# ESC_BOARD_NEW.net
KiCad netlist of a schematic drawn in EAGLE
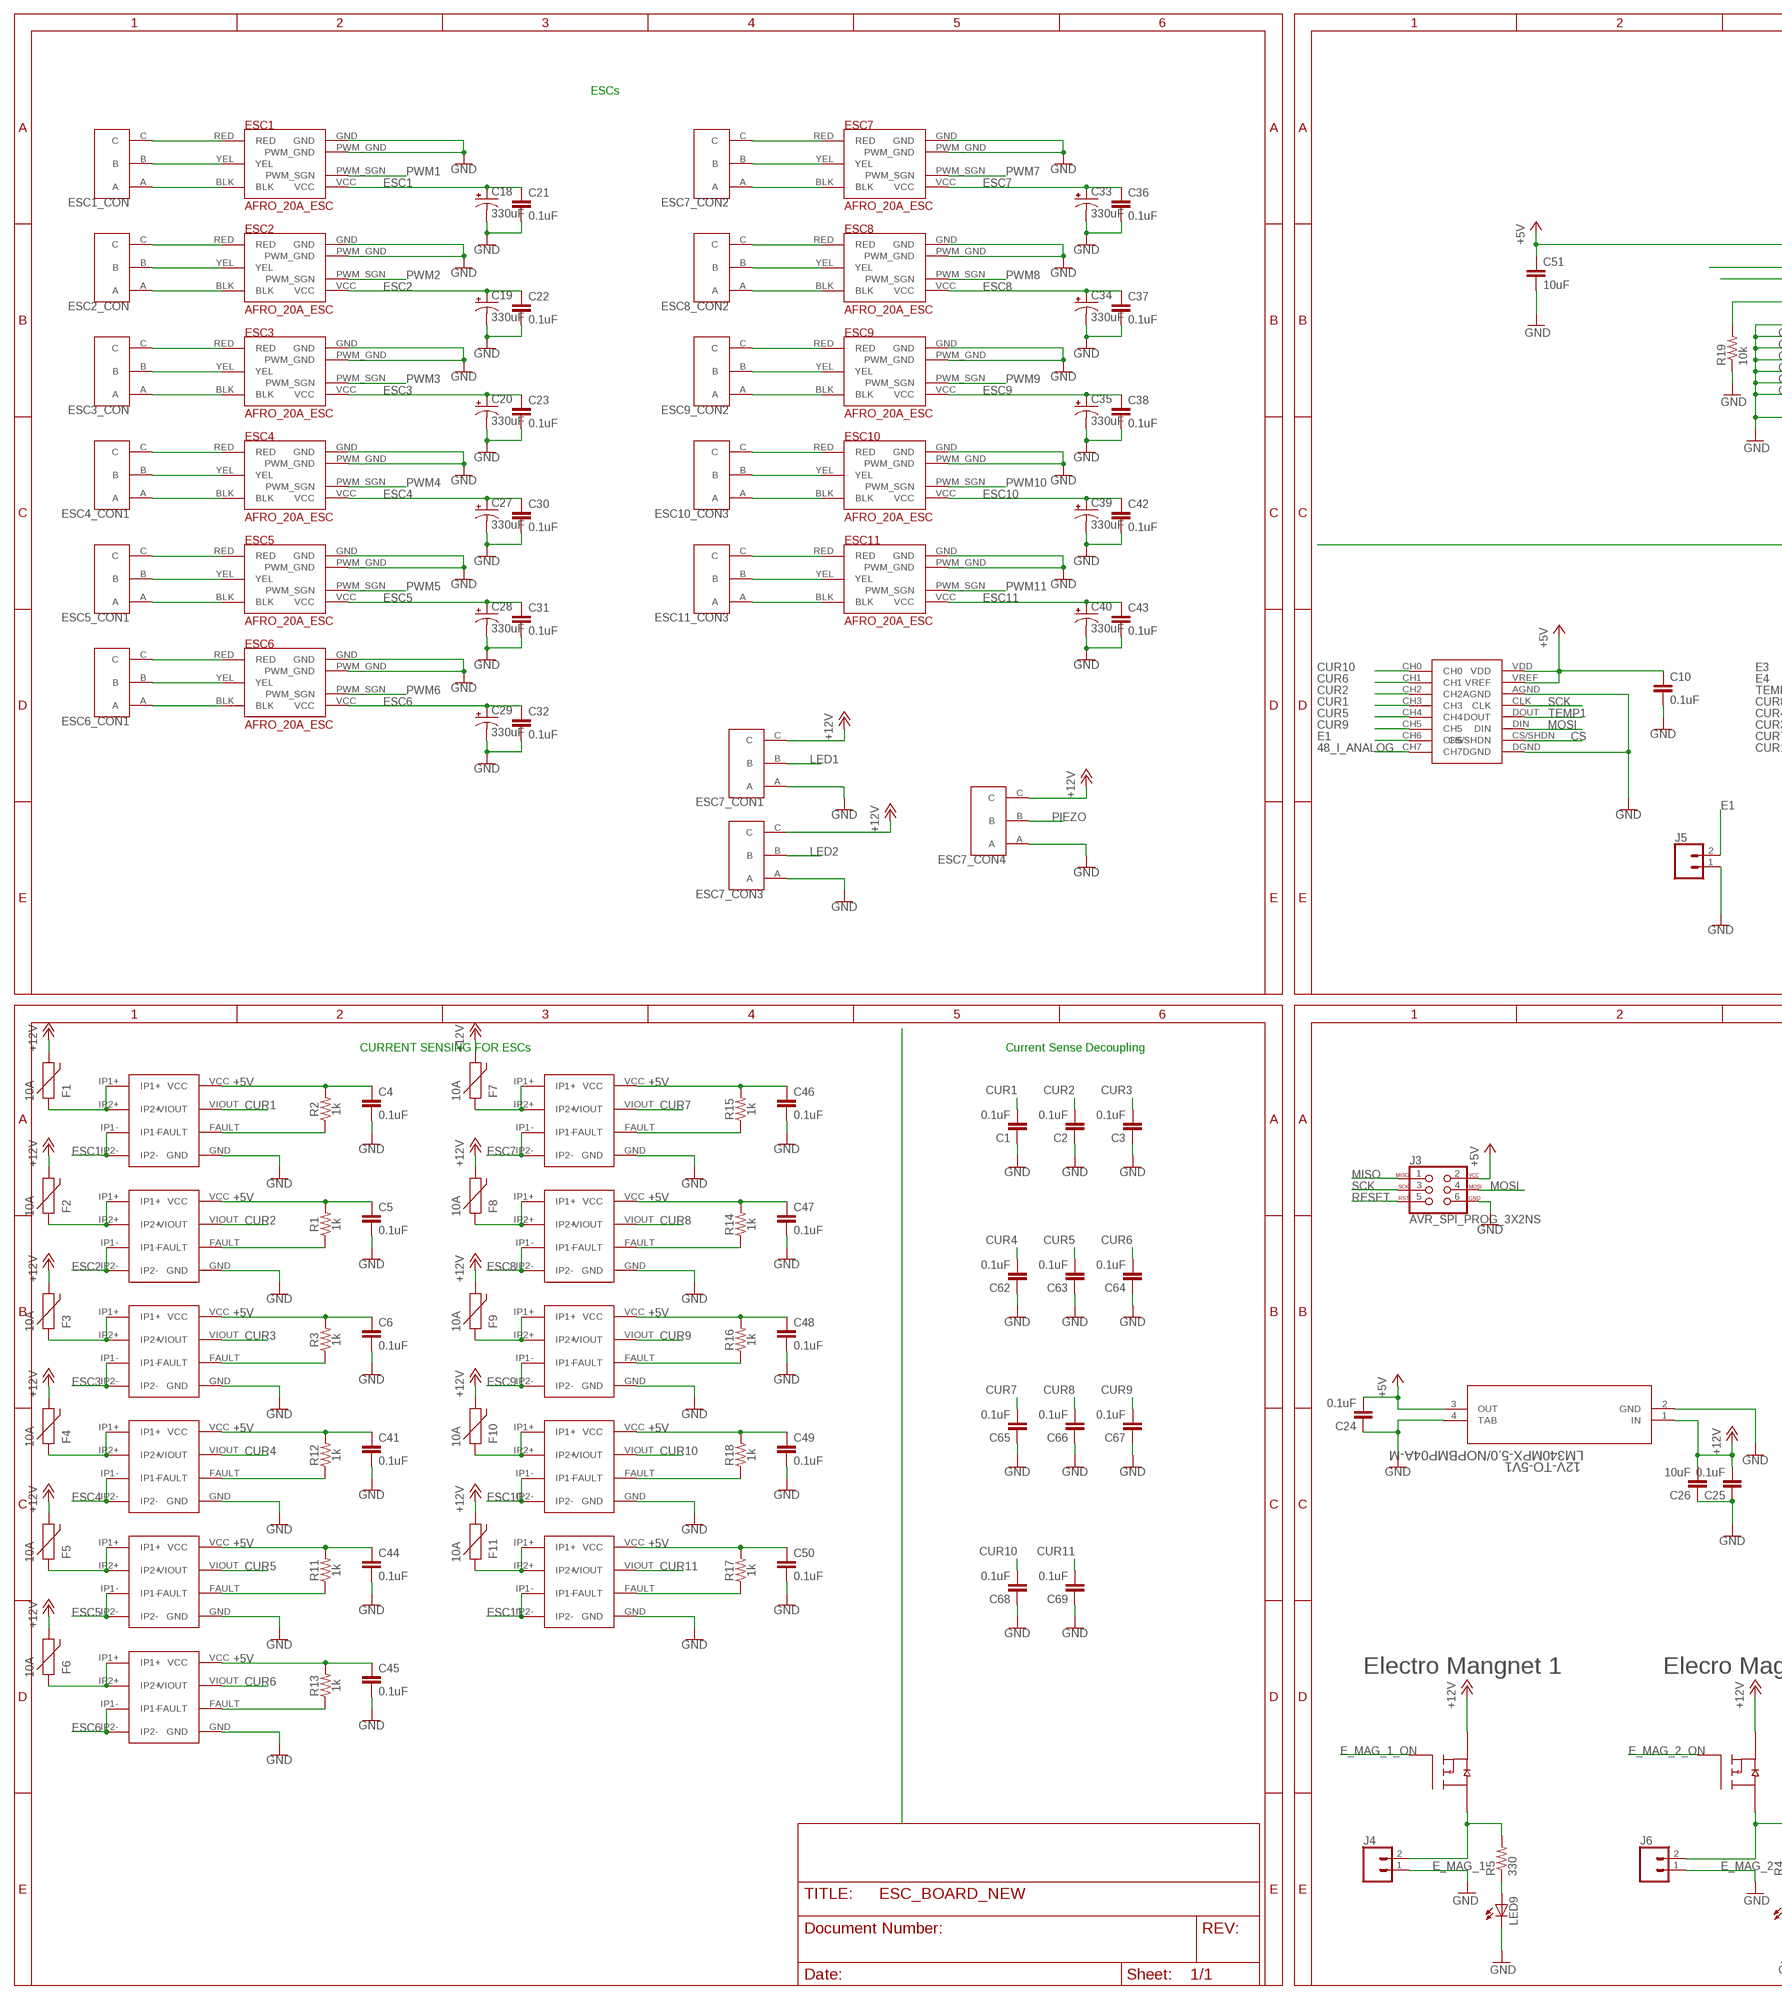
[diagram p0: schematic, sheet 1, part 1 of 2]
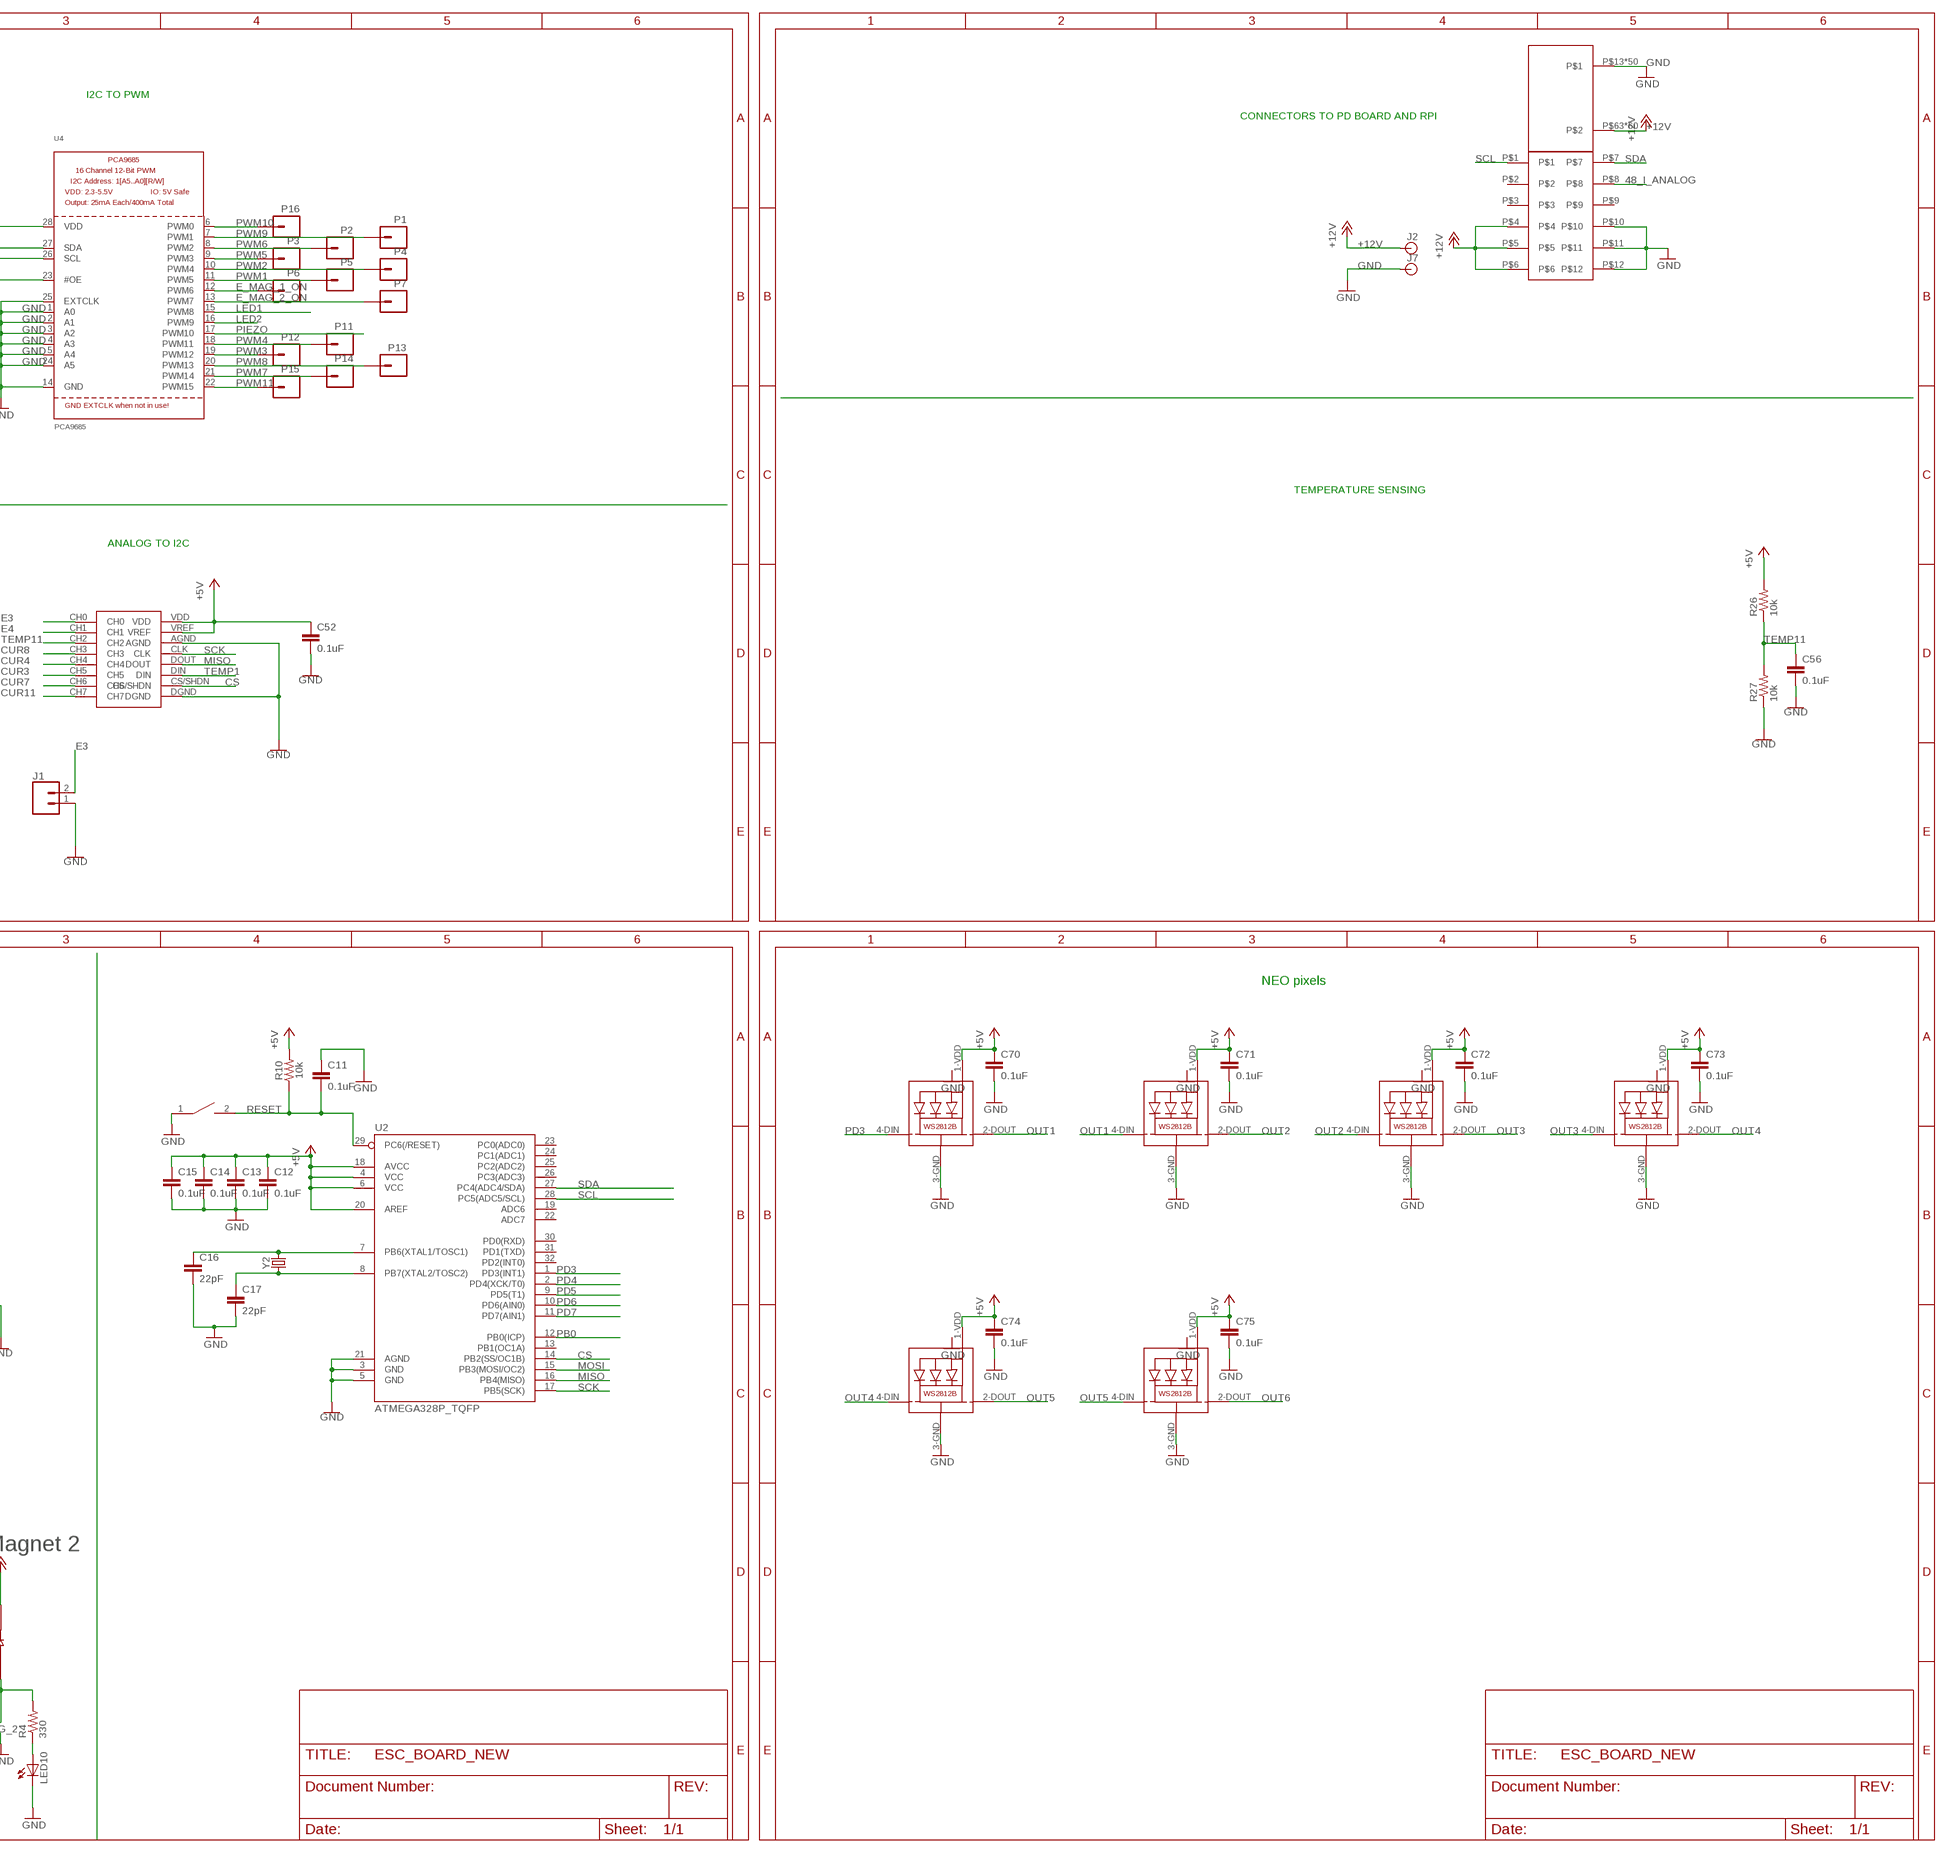
[diagram p1: schematic, sheet 1, part 2 of 2]

(export (version "E")
  (design (tool "Eeschema 10.0.6"))
  (components
    (comp (ref "12V-TO-5V1")
      (value "LM340MPX-5.0/NOPBMP04A-M")
      (footprint "eagle-import:MP04A-M")
      (fields (field (name "MANUFACTURER_PART_NUMBER") "LM340MPX5.0NOPB"))
      (libsource (lib "eagle-import") (part "LM340MPX-5.0/NOPBMP04A-M"))
    )
    (comp (ref "C1")
      (value "0.1uF")
      (footprint "eagle-import:0603")
      (libsource (lib "eagle-import") (part "0.1UF-0603-25V-(+80/-20%)"))
    )
    (comp (ref "C2")
      (value "0.1uF")
      (footprint "eagle-import:0603")
      (libsource (lib "eagle-import") (part "0.1UF-0603-25V-(+80/-20%)"))
    )
    (comp (ref "C3")
      (value "0.1uF")
      (footprint "eagle-import:0603")
      (libsource (lib "eagle-import") (part "0.1UF-0603-25V-(+80/-20%)"))
    )
    (comp (ref "C4")
      (value "0.1uF")
      (footprint "eagle-import:0603")
      (libsource (lib "eagle-import") (part "0.1UF-0603-25V-(+80/-20%)"))
    )
    (comp (ref "C5")
      (value "0.1uF")
      (footprint "eagle-import:0603")
      (libsource (lib "eagle-import") (part "0.1UF-0603-25V-(+80/-20%)"))
    )
    (comp (ref "C6")
      (value "0.1uF")
      (footprint "eagle-import:0603")
      (libsource (lib "eagle-import") (part "0.1UF-0603-25V-(+80/-20%)"))
    )
    (comp (ref "C10")
      (value "0.1uF")
      (footprint "eagle-import:0603")
      (libsource (lib "eagle-import") (part "0.1UF-0603-25V-(+80/-20%)"))
    )
    (comp (ref "C11")
      (value "0.1uF")
      (footprint "eagle-import:C0603")
      (libsource (lib "eagle-import") (part "C-EUC0603"))
    )
    (comp (ref "C12")
      (value "0.1uF")
      (footprint "eagle-import:C0603")
      (libsource (lib "eagle-import") (part "C-EUC0603"))
    )
    (comp (ref "C13")
      (value "0.1uF")
      (footprint "eagle-import:C0603")
      (libsource (lib "eagle-import") (part "C-EUC0603"))
    )
    (comp (ref "C14")
      (value "0.1uF")
      (footprint "eagle-import:C0603")
      (libsource (lib "eagle-import") (part "C-EUC0603"))
    )
    (comp (ref "C15")
      (value "0.1uF")
      (footprint "eagle-import:C0603")
      (libsource (lib "eagle-import") (part "C-EUC0603"))
    )
    (comp (ref "C16")
      (value "22pF")
      (footprint "eagle-import:C0603")
      (libsource (lib "eagle-import") (part "C-EUC0603"))
    )
    (comp (ref "C17")
      (value "22pF")
      (footprint "eagle-import:C0603")
      (libsource (lib "eagle-import") (part "C-EUC0603"))
    )
    (comp (ref "C18")
      (value "330uF")
      (footprint "eagle-import:CPOL-US(10.3_10.3MM)")
      (libsource (lib "eagle-import") (part "C-ALUMINUM(330UF)"))
    )
    (comp (ref "C19")
      (value "330uF")
      (footprint "eagle-import:CPOL-US(10.3_10.3MM)")
      (libsource (lib "eagle-import") (part "C-ALUMINUM(330UF)"))
    )
    (comp (ref "C20")
      (value "330uF")
      (footprint "eagle-import:CPOL-US(10.3_10.3MM)")
      (libsource (lib "eagle-import") (part "C-ALUMINUM(330UF)"))
    )
    (comp (ref "C21")
      (value "0.1uF")
      (footprint "eagle-import:0603")
      (libsource (lib "eagle-import") (part "0.1UF-0603-25V-(+80/-20%)"))
    )
    (comp (ref "C22")
      (value "0.1uF")
      (footprint "eagle-import:0603")
      (libsource (lib "eagle-import") (part "0.1UF-0603-25V-(+80/-20%)"))
    )
    (comp (ref "C23")
      (value "0.1uF")
      (footprint "eagle-import:0603")
      (libsource (lib "eagle-import") (part "0.1UF-0603-25V-(+80/-20%)"))
    )
    (comp (ref "C24")
      (value "0.1uF")
      (footprint "eagle-import:0603")
      (libsource (lib "eagle-import") (part "0.1UF-0603-25V-(+80/-20%)"))
    )
    (comp (ref "C25")
      (value "0.1uF")
      (footprint "eagle-import:0603")
      (libsource (lib "eagle-import") (part "0.1UF-0603-25V-(+80/-20%)"))
    )
    (comp (ref "C26")
      (value "10uF")
      (footprint "eagle-import:0603")
      (libsource (lib "eagle-import") (part "0.1UF-0603-25V-(+80/-20%)"))
    )
    (comp (ref "C27")
      (value "330uF")
      (footprint "eagle-import:CPOL-US(10.3_10.3MM)")
      (libsource (lib "eagle-import") (part "C-ALUMINUM(330UF)"))
    )
    (comp (ref "C28")
      (value "330uF")
      (footprint "eagle-import:CPOL-US(10.3_10.3MM)")
      (libsource (lib "eagle-import") (part "C-ALUMINUM(330UF)"))
    )
    (comp (ref "C29")
      (value "330uF")
      (footprint "eagle-import:CPOL-US(10.3_10.3MM)")
      (libsource (lib "eagle-import") (part "C-ALUMINUM(330UF)"))
    )
    (comp (ref "C30")
      (value "0.1uF")
      (footprint "eagle-import:0603")
      (libsource (lib "eagle-import") (part "0.1UF-0603-25V-(+80/-20%)"))
    )
    (comp (ref "C31")
      (value "0.1uF")
      (footprint "eagle-import:0603")
      (libsource (lib "eagle-import") (part "0.1UF-0603-25V-(+80/-20%)"))
    )
    (comp (ref "C32")
      (value "0.1uF")
      (footprint "eagle-import:0603")
      (libsource (lib "eagle-import") (part "0.1UF-0603-25V-(+80/-20%)"))
    )
    (comp (ref "C33")
      (value "330uF")
      (footprint "eagle-import:CPOL-US(10.3_10.3MM)")
      (libsource (lib "eagle-import") (part "C-ALUMINUM(330UF)"))
    )
    (comp (ref "C34")
      (value "330uF")
      (footprint "eagle-import:CPOL-US(10.3_10.3MM)")
      (libsource (lib "eagle-import") (part "C-ALUMINUM(330UF)"))
    )
    (comp (ref "C35")
      (value "330uF")
      (footprint "eagle-import:CPOL-US(10.3_10.3MM)")
      (libsource (lib "eagle-import") (part "C-ALUMINUM(330UF)"))
    )
    (comp (ref "C36")
      (value "0.1uF")
      (footprint "eagle-import:0603")
      (libsource (lib "eagle-import") (part "0.1UF-0603-25V-(+80/-20%)"))
    )
    (comp (ref "C37")
      (value "0.1uF")
      (footprint "eagle-import:0603")
      (libsource (lib "eagle-import") (part "0.1UF-0603-25V-(+80/-20%)"))
    )
    (comp (ref "C38")
      (value "0.1uF")
      (footprint "eagle-import:0603")
      (libsource (lib "eagle-import") (part "0.1UF-0603-25V-(+80/-20%)"))
    )
    (comp (ref "C39")
      (value "330uF")
      (footprint "eagle-import:CPOL-US(10.3_10.3MM)")
      (libsource (lib "eagle-import") (part "C-ALUMINUM(330UF)"))
    )
    (comp (ref "C40")
      (value "330uF")
      (footprint "eagle-import:CPOL-US(10.3_10.3MM)")
      (libsource (lib "eagle-import") (part "C-ALUMINUM(330UF)"))
    )
    (comp (ref "C41")
      (value "0.1uF")
      (footprint "eagle-import:0603")
      (libsource (lib "eagle-import") (part "0.1UF-0603-25V-(+80/-20%)"))
    )
    (comp (ref "C42")
      (value "0.1uF")
      (footprint "eagle-import:0603")
      (libsource (lib "eagle-import") (part "0.1UF-0603-25V-(+80/-20%)"))
    )
    (comp (ref "C43")
      (value "0.1uF")
      (footprint "eagle-import:0603")
      (libsource (lib "eagle-import") (part "0.1UF-0603-25V-(+80/-20%)"))
    )
    (comp (ref "C44")
      (value "0.1uF")
      (footprint "eagle-import:0603")
      (libsource (lib "eagle-import") (part "0.1UF-0603-25V-(+80/-20%)"))
    )
    (comp (ref "C45")
      (value "0.1uF")
      (footprint "eagle-import:0603")
      (libsource (lib "eagle-import") (part "0.1UF-0603-25V-(+80/-20%)"))
    )
    (comp (ref "C46")
      (value "0.1uF")
      (footprint "eagle-import:0603")
      (libsource (lib "eagle-import") (part "0.1UF-0603-25V-(+80/-20%)"))
    )
    (comp (ref "C47")
      (value "0.1uF")
      (footprint "eagle-import:0603")
      (libsource (lib "eagle-import") (part "0.1UF-0603-25V-(+80/-20%)"))
    )
    (comp (ref "C48")
      (value "0.1uF")
      (footprint "eagle-import:0603")
      (libsource (lib "eagle-import") (part "0.1UF-0603-25V-(+80/-20%)"))
    )
    (comp (ref "C49")
      (value "0.1uF")
      (footprint "eagle-import:0603")
      (libsource (lib "eagle-import") (part "0.1UF-0603-25V-(+80/-20%)"))
    )
    (comp (ref "C50")
      (value "0.1uF")
      (footprint "eagle-import:0603")
      (libsource (lib "eagle-import") (part "0.1UF-0603-25V-(+80/-20%)"))
    )
    (comp (ref "C51")
      (value "10uF")
      (footprint "eagle-import:0603-CAP")
      (libsource (lib "eagle-import") (part "0.1UF-25V(+80/-20%)(0603)"))
    )
    (comp (ref "C52")
      (value "0.1uF")
      (footprint "eagle-import:0603")
      (libsource (lib "eagle-import") (part "0.1UF-0603-25V-(+80/-20%)"))
    )
    (comp (ref "C56")
      (value "0.1uF")
      (footprint "eagle-import:0603")
      (libsource (lib "eagle-import") (part "0.1UF-0603-25V-(+80/-20%)"))
    )
    (comp (ref "C62")
      (value "0.1uF")
      (footprint "eagle-import:0603")
      (libsource (lib "eagle-import") (part "0.1UF-0603-25V-(+80/-20%)"))
    )
    (comp (ref "C63")
      (value "0.1uF")
      (footprint "eagle-import:0603")
      (libsource (lib "eagle-import") (part "0.1UF-0603-25V-(+80/-20%)"))
    )
    (comp (ref "C64")
      (value "0.1uF")
      (footprint "eagle-import:0603")
      (libsource (lib "eagle-import") (part "0.1UF-0603-25V-(+80/-20%)"))
    )
    (comp (ref "C65")
      (value "0.1uF")
      (footprint "eagle-import:0603")
      (libsource (lib "eagle-import") (part "0.1UF-0603-25V-(+80/-20%)"))
    )
    (comp (ref "C66")
      (value "0.1uF")
      (footprint "eagle-import:0603")
      (libsource (lib "eagle-import") (part "0.1UF-0603-25V-(+80/-20%)"))
    )
    (comp (ref "C67")
      (value "0.1uF")
      (footprint "eagle-import:0603")
      (libsource (lib "eagle-import") (part "0.1UF-0603-25V-(+80/-20%)"))
    )
    (comp (ref "C68")
      (value "0.1uF")
      (footprint "eagle-import:0603")
      (libsource (lib "eagle-import") (part "0.1UF-0603-25V-(+80/-20%)"))
    )
    (comp (ref "C69")
      (value "0.1uF")
      (footprint "eagle-import:0603")
      (libsource (lib "eagle-import") (part "0.1UF-0603-25V-(+80/-20%)"))
    )
    (comp (ref "C70")
      (value "0.1uF")
      (footprint "eagle-import:C0603")
      (libsource (lib "eagle-import") (part "C-EUC0603"))
    )
    (comp (ref "C71")
      (value "0.1uF")
      (footprint "eagle-import:C0603")
      (libsource (lib "eagle-import") (part "C-EUC0603"))
    )
    (comp (ref "C72")
      (value "0.1uF")
      (footprint "eagle-import:C0603")
      (libsource (lib "eagle-import") (part "C-EUC0603"))
    )
    (comp (ref "C73")
      (value "0.1uF")
      (footprint "eagle-import:C0603")
      (libsource (lib "eagle-import") (part "C-EUC0603"))
    )
    (comp (ref "C74")
      (value "0.1uF")
      (footprint "eagle-import:C0603")
      (libsource (lib "eagle-import") (part "C-EUC0603"))
    )
    (comp (ref "C75")
      (value "0.1uF")
      (footprint "eagle-import:C0603")
      (libsource (lib "eagle-import") (part "C-EUC0603"))
    )
    (comp (ref "ESC1")
      (value "AFRO_20A_ESC")
      (footprint "eagle-import:AFRO_20A_ESC")
      (libsource (lib "eagle-import") (part "AFRO_20A_ESC"))
    )
    (comp (ref "ESC1_CON")
      (value "3PINCONNECTOR")
      (footprint "eagle-import:3PINCONNECTOR")
      (libsource (lib "eagle-import") (part "3PINCONNECTOR"))
    )
    (comp (ref "ESC2")
      (value "AFRO_20A_ESC")
      (footprint "eagle-import:AFRO_20A_ESC")
      (libsource (lib "eagle-import") (part "AFRO_20A_ESC"))
    )
    (comp (ref "ESC2_CON")
      (value "3PINCONNECTOR")
      (footprint "eagle-import:3PINCONNECTOR")
      (libsource (lib "eagle-import") (part "3PINCONNECTOR"))
    )
    (comp (ref "ESC3")
      (value "AFRO_20A_ESC")
      (footprint "eagle-import:AFRO_20A_ESC")
      (libsource (lib "eagle-import") (part "AFRO_20A_ESC"))
    )
    (comp (ref "ESC3_CON")
      (value "3PINCONNECTOR")
      (footprint "eagle-import:3PINCONNECTOR")
      (libsource (lib "eagle-import") (part "3PINCONNECTOR"))
    )
    (comp (ref "ESC4")
      (value "AFRO_20A_ESC")
      (footprint "eagle-import:AFRO_20A_ESC")
      (libsource (lib "eagle-import") (part "AFRO_20A_ESC"))
    )
    (comp (ref "ESC4_CON1")
      (value "3PINCONNECTOR")
      (footprint "eagle-import:3PINCONNECTOR")
      (libsource (lib "eagle-import") (part "3PINCONNECTOR"))
    )
    (comp (ref "ESC5")
      (value "AFRO_20A_ESC")
      (footprint "eagle-import:AFRO_20A_ESC")
      (libsource (lib "eagle-import") (part "AFRO_20A_ESC"))
    )
    (comp (ref "ESC5_CON1")
      (value "3PINCONNECTOR")
      (footprint "eagle-import:3PINCONNECTOR")
      (libsource (lib "eagle-import") (part "3PINCONNECTOR"))
    )
    (comp (ref "ESC6")
      (value "AFRO_20A_ESC")
      (footprint "eagle-import:AFRO_20A_ESC")
      (libsource (lib "eagle-import") (part "AFRO_20A_ESC"))
    )
    (comp (ref "ESC6_CON1")
      (value "3PINCONNECTOR")
      (footprint "eagle-import:3PINCONNECTOR")
      (libsource (lib "eagle-import") (part "3PINCONNECTOR"))
    )
    (comp (ref "ESC7")
      (value "AFRO_20A_ESC")
      (footprint "eagle-import:AFRO_20A_ESC")
      (libsource (lib "eagle-import") (part "AFRO_20A_ESC"))
    )
    (comp (ref "ESC7_CON1")
      (value "3PINCONNECTOR")
      (footprint "eagle-import:3PINCONNECTOR")
      (libsource (lib "eagle-import") (part "3PINCONNECTOR"))
    )
    (comp (ref "ESC7_CON2")
      (value "3PINCONNECTOR")
      (footprint "eagle-import:3PINCONNECTOR")
      (libsource (lib "eagle-import") (part "3PINCONNECTOR"))
    )
    (comp (ref "ESC7_CON3")
      (value "3PINCONNECTOR")
      (footprint "eagle-import:3PINCONNECTOR")
      (libsource (lib "eagle-import") (part "3PINCONNECTOR"))
    )
    (comp (ref "ESC7_CON4")
      (value "3PINCONNECTOR")
      (footprint "eagle-import:3PINCONNECTOR")
      (libsource (lib "eagle-import") (part "3PINCONNECTOR"))
    )
    (comp (ref "ESC8")
      (value "AFRO_20A_ESC")
      (footprint "eagle-import:AFRO_20A_ESC")
      (libsource (lib "eagle-import") (part "AFRO_20A_ESC"))
    )
    (comp (ref "ESC8_CON2")
      (value "3PINCONNECTOR")
      (footprint "eagle-import:3PINCONNECTOR")
      (libsource (lib "eagle-import") (part "3PINCONNECTOR"))
    )
    (comp (ref "ESC9")
      (value "AFRO_20A_ESC")
      (footprint "eagle-import:AFRO_20A_ESC")
      (libsource (lib "eagle-import") (part "AFRO_20A_ESC"))
    )
    (comp (ref "ESC9_CON2")
      (value "3PINCONNECTOR")
      (footprint "eagle-import:3PINCONNECTOR")
      (libsource (lib "eagle-import") (part "3PINCONNECTOR"))
    )
    (comp (ref "ESC10")
      (value "AFRO_20A_ESC")
      (footprint "eagle-import:AFRO_20A_ESC")
      (libsource (lib "eagle-import") (part "AFRO_20A_ESC"))
    )
    (comp (ref "ESC10_CON3")
      (value "3PINCONNECTOR")
      (footprint "eagle-import:3PINCONNECTOR")
      (libsource (lib "eagle-import") (part "3PINCONNECTOR"))
    )
    (comp (ref "ESC11")
      (value "AFRO_20A_ESC")
      (footprint "eagle-import:AFRO_20A_ESC")
      (libsource (lib "eagle-import") (part "AFRO_20A_ESC"))
    )
    (comp (ref "ESC11_CON3")
      (value "3PINCONNECTOR")
      (footprint "eagle-import:3PINCONNECTOR")
      (libsource (lib "eagle-import") (part "3PINCONNECTOR"))
    )
    (comp (ref "F1")
      (value "10A")
      (footprint "eagle-import:PTC-2920")
      (libsource (lib "eagle-import") (part "PTC(2920L)"))
    )
    (comp (ref "F2")
      (value "10A")
      (footprint "eagle-import:PTC-2920")
      (libsource (lib "eagle-import") (part "PTC(2920L)"))
    )
    (comp (ref "F3")
      (value "10A")
      (footprint "eagle-import:PTC-2920")
      (libsource (lib "eagle-import") (part "PTC(2920L)"))
    )
    (comp (ref "F4")
      (value "10A")
      (footprint "eagle-import:PTC-2920")
      (libsource (lib "eagle-import") (part "PTC(2920L)"))
    )
    (comp (ref "F5")
      (value "10A")
      (footprint "eagle-import:PTC-2920")
      (libsource (lib "eagle-import") (part "PTC(2920L)"))
    )
    (comp (ref "F6")
      (value "10A")
      (footprint "eagle-import:PTC-2920")
      (libsource (lib "eagle-import") (part "PTC(2920L)"))
    )
    (comp (ref "F7")
      (value "10A")
      (footprint "eagle-import:PTC-2920")
      (libsource (lib "eagle-import") (part "PTC(2920L)"))
    )
    (comp (ref "F8")
      (value "10A")
      (footprint "eagle-import:PTC-2920")
      (libsource (lib "eagle-import") (part "PTC(2920L)"))
    )
    (comp (ref "F9")
      (value "10A")
      (footprint "eagle-import:PTC-2920")
      (libsource (lib "eagle-import") (part "PTC(2920L)"))
    )
    (comp (ref "F10")
      (value "10A")
      (footprint "eagle-import:PTC-2920")
      (libsource (lib "eagle-import") (part "PTC(2920L)"))
    )
    (comp (ref "F11")
      (value "10A")
      (footprint "eagle-import:PTC-2920")
      (libsource (lib "eagle-import") (part "PTC(2920L)"))
    )
    (comp (ref "J1")
      (value "CONN_02")
      (footprint "eagle-import:1X02")
      (libsource (lib "eagle-import") (part "CONN_02"))
    )
    (comp (ref "J2")
      (value "BANANA_CONN")
      (footprint "eagle-import:BANANA_CONN")
      (libsource (lib "eagle-import") (part "BANANA_CONN"))
    )
    (comp (ref "J3")
      (value "AVR_SPI_PROG_3X2NS")
      (footprint "eagle-import:2X3-NS")
      (libsource (lib "eagle-import") (part "AVR_SPI_PROG_3X2NS"))
    )
    (comp (ref "J4")
      (value "CONN_02")
      (footprint "eagle-import:1X02")
      (libsource (lib "eagle-import") (part "SparkFun-Connectors_513_CONN_02"))
    )
    (comp (ref "J5")
      (value "CONN_02")
      (footprint "eagle-import:1X02")
      (libsource (lib "eagle-import") (part "CONN_02"))
    )
    (comp (ref "J6")
      (value "CONN_02")
      (footprint "eagle-import:1X02")
      (libsource (lib "eagle-import") (part "SparkFun-Connectors_513_CONN_02"))
    )
    (comp (ref "J7")
      (value "BANANA_CONN")
      (footprint "eagle-import:BANANA_CONN")
      (libsource (lib "eagle-import") (part "BANANA_CONN"))
    )
    (comp (ref "LED1")
      (value "WS2812B5050")
      (footprint "eagle-import:WS2812B")
      (libsource (lib "eagle-import") (part "WS2812B5050"))
    )
    (comp (ref "LED2")
      (value "WS2812B5050")
      (footprint "eagle-import:WS2812B")
      (libsource (lib "eagle-import") (part "WS2812B5050"))
    )
    (comp (ref "LED3")
      (value "WS2812B5050")
      (footprint "eagle-import:WS2812B")
      (libsource (lib "eagle-import") (part "WS2812B5050"))
    )
    (comp (ref "LED4")
      (value "WS2812B5050")
      (footprint "eagle-import:WS2812B")
      (libsource (lib "eagle-import") (part "WS2812B5050"))
    )
    (comp (ref "LED5")
      (value "WS2812B5050")
      (footprint "eagle-import:WS2812B")
      (libsource (lib "eagle-import") (part "WS2812B5050"))
    )
    (comp (ref "LED6")
      (value "WS2812B5050")
      (footprint "eagle-import:WS2812B")
      (libsource (lib "eagle-import") (part "WS2812B5050"))
    )
    (comp (ref "LED9")
      (value "LEDSML0603")
      (footprint "eagle-import:SML0603")
      (libsource (lib "eagle-import") (part "LEDSML0603"))
    )
    (comp (ref "LED10")
      (value "LEDSML0603")
      (footprint "eagle-import:SML0603")
      (libsource (lib "eagle-import") (part "LEDSML0603"))
    )
    (comp (ref "P1")
      (value "M01PTH")
      (footprint "eagle-import:1X01")
      (libsource (lib "eagle-import") (part "M01PTH"))
    )
    (comp (ref "P2")
      (value "M01PTH")
      (footprint "eagle-import:1X01")
      (libsource (lib "eagle-import") (part "M01PTH"))
    )
    (comp (ref "P3")
      (value "M01PTH")
      (footprint "eagle-import:1X01")
      (libsource (lib "eagle-import") (part "M01PTH"))
    )
    (comp (ref "P4")
      (value "M01PTH")
      (footprint "eagle-import:1X01")
      (libsource (lib "eagle-import") (part "M01PTH"))
    )
    (comp (ref "P5")
      (value "M01PTH")
      (footprint "eagle-import:1X01")
      (libsource (lib "eagle-import") (part "M01PTH"))
    )
    (comp (ref "P6")
      (value "M01PTH")
      (footprint "eagle-import:1X01")
      (libsource (lib "eagle-import") (part "M01PTH"))
    )
    (comp (ref "P7")
      (value "M01PTH")
      (footprint "eagle-import:1X01")
      (libsource (lib "eagle-import") (part "M01PTH"))
    )
    (comp (ref "P11")
      (value "M01PTH")
      (footprint "eagle-import:1X01")
      (libsource (lib "eagle-import") (part "M01PTH"))
    )
    (comp (ref "P12")
      (value "M01PTH")
      (footprint "eagle-import:1X01")
      (libsource (lib "eagle-import") (part "M01PTH"))
    )
    (comp (ref "P13")
      (value "M01PTH")
      (footprint "eagle-import:1X01")
      (libsource (lib "eagle-import") (part "M01PTH"))
    )
    (comp (ref "P14")
      (value "M01PTH")
      (footprint "eagle-import:1X01")
      (libsource (lib "eagle-import") (part "M01PTH"))
    )
    (comp (ref "P15")
      (value "M01PTH")
      (footprint "eagle-import:1X01")
      (libsource (lib "eagle-import") (part "M01PTH"))
    )
    (comp (ref "P16")
      (value "M01PTH")
      (footprint "eagle-import:1X01")
      (libsource (lib "eagle-import") (part "M01PTH"))
    )
    (comp (ref "R1")
      (value "1k")
      (footprint "eagle-import:0603")
      (libsource (lib "eagle-import") (part "1KOHM-0603-1/10W-1%"))
    )
    (comp (ref "R2")
      (value "1k")
      (footprint "eagle-import:0603")
      (libsource (lib "eagle-import") (part "1KOHM-0603-1/10W-1%"))
    )
    (comp (ref "R3")
      (value "1k")
      (footprint "eagle-import:0603")
      (libsource (lib "eagle-import") (part "1KOHM-0603-1/10W-1%"))
    )
    (comp (ref "R4")
      (value "330")
      (footprint "eagle-import:R0603")
      (libsource (lib "eagle-import") (part "resistor_R-US_R0603"))
    )
    (comp (ref "R5")
      (value "330")
      (footprint "eagle-import:R0603")
      (libsource (lib "eagle-import") (part "resistor_R-US_R0603"))
    )
    (comp (ref "R10")
      (value "10k")
      (footprint "eagle-import:0603")
      (libsource (lib "eagle-import") (part "RESISTOR0603"))
    )
    (comp (ref "R11")
      (value "1k")
      (footprint "eagle-import:0603")
      (libsource (lib "eagle-import") (part "1KOHM-0603-1/10W-1%"))
    )
    (comp (ref "R12")
      (value "1k")
      (footprint "eagle-import:0603")
      (libsource (lib "eagle-import") (part "1KOHM-0603-1/10W-1%"))
    )
    (comp (ref "R13")
      (value "1k")
      (footprint "eagle-import:0603")
      (libsource (lib "eagle-import") (part "1KOHM-0603-1/10W-1%"))
    )
    (comp (ref "R14")
      (value "1k")
      (footprint "eagle-import:0603")
      (libsource (lib "eagle-import") (part "1KOHM-0603-1/10W-1%"))
    )
    (comp (ref "R15")
      (value "1k")
      (footprint "eagle-import:0603")
      (libsource (lib "eagle-import") (part "1KOHM-0603-1/10W-1%"))
    )
    (comp (ref "R16")
      (value "1k")
      (footprint "eagle-import:0603")
      (libsource (lib "eagle-import") (part "1KOHM-0603-1/10W-1%"))
    )
    (comp (ref "R17")
      (value "1k")
      (footprint "eagle-import:0603")
      (libsource (lib "eagle-import") (part "1KOHM-0603-1/10W-1%"))
    )
    (comp (ref "R18")
      (value "1k")
      (footprint "eagle-import:0603")
      (libsource (lib "eagle-import") (part "1KOHM-0603-1/10W-1%"))
    )
    (comp (ref "R19")
      (value "10k")
      (footprint "eagle-import:0603-RES")
      (libsource (lib "eagle-import") (part "470OHM1/10W1%(0603)"))
    )
    (comp (ref "R26")
      (value "10k")
      (footprint "eagle-import:R0603")
      (libsource (lib "eagle-import") (part "R-US_R0603"))
    )
    (comp (ref "R27")
      (value "10k")
      (footprint "eagle-import:R0603")
      (libsource (lib "eagle-import") (part "R-US_R0603"))
    )
    (comp (ref "RESET")
      (value "SWITCH")
      (footprint "eagle-import:SW_2512")
      (libsource (lib "eagle-import") (part "SWITCH"))
    )
    (comp (ref "U$1")
      (value "ACS711")
      (footprint "eagle-import:ACS711")
      (libsource (lib "eagle-import") (part "ACS711"))
    )
    (comp (ref "U$2")
      (value "ACS711")
      (footprint "eagle-import:ACS711")
      (libsource (lib "eagle-import") (part "ACS711"))
    )
    (comp (ref "U$3")
      (value "ACS711")
      (footprint "eagle-import:ACS711")
      (libsource (lib "eagle-import") (part "ACS711"))
    )
    (comp (ref "U$4")
      (value "MCP3008")
      (footprint "eagle-import:MCP3008")
      (libsource (lib "eagle-import") (part "MCP3008"))
    )
    (comp (ref "U$5")
      (value "ACS711")
      (footprint "eagle-import:ACS711")
      (libsource (lib "eagle-import") (part "ACS711"))
    )
    (comp (ref "U$6")
      (value "ACS711")
      (footprint "eagle-import:ACS711")
      (libsource (lib "eagle-import") (part "ACS711"))
    )
    (comp (ref "U$7")
      (value "ACS711")
      (footprint "eagle-import:ACS711")
      (libsource (lib "eagle-import") (part "ACS711"))
    )
    (comp (ref "U$8")
      (value "ACS711")
      (footprint "eagle-import:ACS711")
      (libsource (lib "eagle-import") (part "ACS711"))
    )
    (comp (ref "U$9")
      (value "ACS711")
      (footprint "eagle-import:ACS711")
      (libsource (lib "eagle-import") (part "ACS711"))
    )
    (comp (ref "U$10")
      (value "ACS711")
      (footprint "eagle-import:ACS711")
      (libsource (lib "eagle-import") (part "ACS711"))
    )
    (comp (ref "U$11")
      (value "ACS711")
      (footprint "eagle-import:ACS711")
      (libsource (lib "eagle-import") (part "ACS711"))
    )
    (comp (ref "U$12")
      (value "ACS711")
      (footprint "eagle-import:ACS711")
      (libsource (lib "eagle-import") (part "ACS711"))
    )
    (comp (ref "U$13")
      (value "MCP3008")
      (footprint "eagle-import:MCP3008")
      (libsource (lib "eagle-import") (part "MCP3008"))
    )
    (comp (ref "U$15")
      (value "ESC-FULL")
      (footprint "eagle-import:ESC-FULL")
      (libsource (lib "eagle-import") (part "ESC-FULL"))
    )
    (comp (ref "U1")
      (value "FQB27P06")
      (footprint "eagle-import:TO263-3")
      (libsource (lib "eagle-import") (part "FQB27P06"))
    )
    (comp (ref "U2")
      (value "ATMEGA328P_TQFP")
      (footprint "eagle-import:TQFP32-08")
      (libsource (lib "eagle-import") (part "ATMEGA328P_TQFP"))
    )
    (comp (ref "U3")
      (value "FQB27P06")
      (footprint "eagle-import:TO263-3")
      (libsource (lib "eagle-import") (part "FQB27P06"))
    )
    (comp (ref "U4")
      (value "PCA9685")
      (footprint "eagle-import:TSSOP28")
      (libsource (lib "eagle-import") (part "PCA9685"))
    )
    (comp (ref "Y2")
      (value "CRYSTALPTH-HC49US")
      (footprint "eagle-import:HC49US")
      (libsource (lib "eagle-import") (part "CRYSTALPTH-HC49US"))
    )
  )
  (nets
    (net (code "1") (name "+5V") (class "Default")
      (node (ref "12V-TO-5V1") (pin "3") (pinfunction "OUT_3") (pintype "power_in"))
      (node (ref "C10") (pin "1") (pinfunction "1_1") (pintype "passive"))
      (node (ref "C12") (pin "1") (pinfunction "1_1") (pintype "passive"))
      (node (ref "C13") (pin "1") (pinfunction "1_1") (pintype "passive"))
      (node (ref "C14") (pin "1") (pinfunction "1_1") (pintype "passive"))
      (node (ref "C15") (pin "1") (pinfunction "1_1") (pintype "passive"))
      (node (ref "C24") (pin "2") (pinfunction "2_2") (pintype "passive"))
      (node (ref "C4") (pin "1") (pinfunction "1_1") (pintype "passive"))
      (node (ref "C41") (pin "1") (pinfunction "1_1") (pintype "passive"))
      (node (ref "C44") (pin "1") (pinfunction "1_1") (pintype "passive"))
      (node (ref "C45") (pin "1") (pinfunction "1_1") (pintype "passive"))
      (node (ref "C46") (pin "1") (pinfunction "1_1") (pintype "passive"))
      (node (ref "C47") (pin "1") (pinfunction "1_1") (pintype "passive"))
      (node (ref "C48") (pin "1") (pinfunction "1_1") (pintype "passive"))
      (node (ref "C49") (pin "1") (pinfunction "1_1") (pintype "passive"))
      (node (ref "C5") (pin "1") (pinfunction "1_1") (pintype "passive"))
      (node (ref "C50") (pin "1") (pinfunction "1_1") (pintype "passive"))
      (node (ref "C51") (pin "1") (pinfunction "1_1") (pintype "passive"))
      (node (ref "C52") (pin "1") (pinfunction "1_1") (pintype "passive"))
      (node (ref "C6") (pin "1") (pinfunction "1_1") (pintype "passive"))
      (node (ref "C70") (pin "1") (pinfunction "1_1") (pintype "passive"))
      (node (ref "C71") (pin "1") (pinfunction "1_1") (pintype "passive"))
      (node (ref "C72") (pin "1") (pinfunction "1_1") (pintype "passive"))
      (node (ref "C73") (pin "1") (pinfunction "1_1") (pintype "passive"))
      (node (ref "C74") (pin "1") (pinfunction "1_1") (pintype "passive"))
      (node (ref "C75") (pin "1") (pinfunction "1_1") (pintype "passive"))
      (node (ref "J3") (pin "2") (pinfunction "2_2") (pintype "passive"))
      (node (ref "LED1") (pin "1-VDD") (pinfunction "VDD_1-VDD") (pintype "power_in"))
      (node (ref "LED2") (pin "1-VDD") (pinfunction "VDD_1-VDD") (pintype "power_in"))
      (node (ref "LED3") (pin "1-VDD") (pinfunction "VDD_1-VDD") (pintype "power_in"))
      (node (ref "LED4") (pin "1-VDD") (pinfunction "VDD_1-VDD") (pintype "power_in"))
      (node (ref "LED5") (pin "1-VDD") (pinfunction "VDD_1-VDD") (pintype "power_in"))
      (node (ref "LED6") (pin "1-VDD") (pinfunction "VDD_1-VDD") (pintype "power_in"))
      (node (ref "R1") (pin "2") (pinfunction "2_2") (pintype "passive"))
      (node (ref "R10") (pin "2") (pinfunction "2_2") (pintype "passive"))
      (node (ref "R11") (pin "2") (pinfunction "2_2") (pintype "passive"))
      (node (ref "R12") (pin "2") (pinfunction "2_2") (pintype "passive"))
      (node (ref "R13") (pin "2") (pinfunction "2_2") (pintype "passive"))
      (node (ref "R14") (pin "2") (pinfunction "2_2") (pintype "passive"))
      (node (ref "R15") (pin "2") (pinfunction "2_2") (pintype "passive"))
      (node (ref "R16") (pin "2") (pinfunction "2_2") (pintype "passive"))
      (node (ref "R17") (pin "2") (pinfunction "2_2") (pintype "passive"))
      (node (ref "R18") (pin "2") (pinfunction "2_2") (pintype "passive"))
      (node (ref "R2") (pin "2") (pinfunction "2_2") (pintype "passive"))
      (node (ref "R26") (pin "2") (pinfunction "2_2") (pintype "passive"))
      (node (ref "R3") (pin "2") (pinfunction "2_2") (pintype "passive"))
      (node (ref "U$1") (pin "VCC") (pinfunction "VCC_VCC") (pintype "bidirectional"))
      (node (ref "U$10") (pin "VCC") (pinfunction "VCC_VCC") (pintype "bidirectional"))
      (node (ref "U$11") (pin "VCC") (pinfunction "VCC_VCC") (pintype "bidirectional"))
      (node (ref "U$12") (pin "VCC") (pinfunction "VCC_VCC") (pintype "bidirectional"))
      (node (ref "U$13") (pin "VDD") (pinfunction "VDD_VDD") (pintype "bidirectional"))
      (node (ref "U$13") (pin "VREF") (pinfunction "VREF_VREF") (pintype "bidirectional"))
      (node (ref "U$2") (pin "VCC") (pinfunction "VCC_VCC") (pintype "bidirectional"))
      (node (ref "U$3") (pin "VCC") (pinfunction "VCC_VCC") (pintype "bidirectional"))
      (node (ref "U$4") (pin "VDD") (pinfunction "VDD_VDD") (pintype "bidirectional"))
      (node (ref "U$4") (pin "VREF") (pinfunction "VREF_VREF") (pintype "bidirectional"))
      (node (ref "U$5") (pin "VCC") (pinfunction "VCC_VCC") (pintype "bidirectional"))
      (node (ref "U$6") (pin "VCC") (pinfunction "VCC_VCC") (pintype "bidirectional"))
      (node (ref "U$7") (pin "VCC") (pinfunction "VCC_VCC") (pintype "bidirectional"))
      (node (ref "U$8") (pin "VCC") (pinfunction "VCC_VCC") (pintype "bidirectional"))
      (node (ref "U$9") (pin "VCC") (pinfunction "VCC_VCC") (pintype "bidirectional"))
      (node (ref "U2") (pin "18") (pinfunction "AVCC_18") (pintype "bidirectional"))
      (node (ref "U2") (pin "20") (pinfunction "AREF_20") (pintype "bidirectional"))
      (node (ref "U2") (pin "4") (pinfunction "VCC_4") (pintype "bidirectional"))
      (node (ref "U2") (pin "6") (pinfunction "VCC_6") (pintype "bidirectional"))
      (node (ref "U4") (pin "28") (pinfunction "VDD_28") (pintype "power_in"))
    )
    (net (code "2") (name "+12V") (class "Default")
      (node (ref "12V-TO-5V1") (pin "1") (pinfunction "IN_1") (pintype "power_in"))
      (node (ref "C25") (pin "2") (pinfunction "2_2") (pintype "passive"))
      (node (ref "C26") (pin "2") (pinfunction "2_2") (pintype "passive"))
      (node (ref "ESC7_CON1") (pin "C") (pinfunction "C_C") (pintype "bidirectional"))
      (node (ref "ESC7_CON3") (pin "C") (pinfunction "C_C") (pintype "bidirectional"))
      (node (ref "ESC7_CON4") (pin "C") (pinfunction "C_C") (pintype "bidirectional"))
      (node (ref "F1") (pin "2") (pinfunction "2_2") (pintype "bidirectional"))
      (node (ref "F10") (pin "2") (pinfunction "2_2") (pintype "bidirectional"))
      (node (ref "F11") (pin "2") (pinfunction "2_2") (pintype "bidirectional"))
      (node (ref "F2") (pin "2") (pinfunction "2_2") (pintype "bidirectional"))
      (node (ref "F3") (pin "2") (pinfunction "2_2") (pintype "bidirectional"))
      (node (ref "F4") (pin "2") (pinfunction "2_2") (pintype "bidirectional"))
      (node (ref "F5") (pin "2") (pinfunction "2_2") (pintype "bidirectional"))
      (node (ref "F6") (pin "2") (pinfunction "2_2") (pintype "bidirectional"))
      (node (ref "F7") (pin "2") (pinfunction "2_2") (pintype "bidirectional"))
      (node (ref "F8") (pin "2") (pinfunction "2_2") (pintype "bidirectional"))
      (node (ref "F9") (pin "2") (pinfunction "2_2") (pintype "bidirectional"))
      (node (ref "J2") (pin "P$1") (pinfunction "1_P$1") (pintype "passive"))
      (node (ref "U$15") (pin "P$101") (pinfunction "P$2_P$101") (pintype "bidirectional"))
      (node (ref "U$15") (pin "P$102") (pinfunction "P$2_P$102") (pintype "bidirectional"))
      (node (ref "U$15") (pin "P$103") (pinfunction "P$2_P$103") (pintype "bidirectional"))
      (node (ref "U$15") (pin "P$104") (pinfunction "P$2_P$104") (pintype "bidirectional"))
      (node (ref "U$15") (pin "P$105") (pinfunction "P$2_P$105") (pintype "bidirectional"))
      (node (ref "U$15") (pin "P$106") (pinfunction "P$2_P$106") (pintype "bidirectional"))
      (node (ref "U$15") (pin "P$107") (pinfunction "P$2_P$107") (pintype "bidirectional"))
      (node (ref "U$15") (pin "P$108") (pinfunction "P$2_P$108") (pintype "bidirectional"))
      (node (ref "U$15") (pin "P$109") (pinfunction "P$2_P$109") (pintype "bidirectional"))
      (node (ref "U$15") (pin "P$110") (pinfunction "P$2_P$110") (pintype "bidirectional"))
      (node (ref "U$15") (pin "P$111") (pinfunction "P$2_P$111") (pintype "bidirectional"))
      (node (ref "U$15") (pin "P$112") (pinfunction "P$2_P$112") (pintype "bidirectional"))
      (node (ref "U$15") (pin "P$113") (pinfunction "P$2_P$113") (pintype "bidirectional"))
      (node (ref "U$15") (pin "P$114") (pinfunction "P$2_P$114") (pintype "bidirectional"))
      (node (ref "U$15") (pin "P$115") (pinfunction "P$2_P$115") (pintype "bidirectional"))
      (node (ref "U$15") (pin "P$116") (pinfunction "P$2_P$116") (pintype "bidirectional"))
      (node (ref "U$15") (pin "P$117") (pinfunction "P$2_P$117") (pintype "bidirectional"))
      (node (ref "U$15") (pin "P$118") (pinfunction "P$2_P$118") (pintype "bidirectional"))
      (node (ref "U$15") (pin "P$119") (pinfunction "P$2_P$119") (pintype "bidirectional"))
      (node (ref "U$15") (pin "P$120") (pinfunction "P$2_P$120") (pintype "bidirectional"))
      (node (ref "U$15") (pin "P$121") (pinfunction "P$2_P$121") (pintype "bidirectional"))
      (node (ref "U$15") (pin "P$122") (pinfunction "P$2_P$122") (pintype "bidirectional"))
      (node (ref "U$15") (pin "P$123") (pinfunction "P$2_P$123") (pintype "bidirectional"))
      (node (ref "U$15") (pin "P$124") (pinfunction "P$2_P$124") (pintype "bidirectional"))
      (node (ref "U$15") (pin "P$125") (pinfunction "P$2_P$125") (pintype "bidirectional"))
      (node (ref "U$15") (pin "P$126") (pinfunction "P$2_P$126") (pintype "bidirectional"))
      (node (ref "U$15") (pin "P$127") (pinfunction "P$2_P$127") (pintype "bidirectional"))
      (node (ref "U$15") (pin "P$128") (pinfunction "P$2_P$128") (pintype "bidirectional"))
      (node (ref "U$15") (pin "P$129") (pinfunction "P$2_P$129") (pintype "bidirectional"))
      (node (ref "U$15") (pin "P$130") (pinfunction "P$2_P$130") (pintype "bidirectional"))
      (node (ref "U$15") (pin "P$4") (pinfunction "P$4_P$4") (pintype "bidirectional"))
      (node (ref "U$15") (pin "P$5") (pinfunction "P$5_P$5") (pintype "bidirectional"))
      (node (ref "U$15") (pin "P$6") (pinfunction "P$6_P$6") (pintype "bidirectional"))
      (node (ref "U$15") (pin "P$63") (pinfunction "P$2_P$63") (pintype "bidirectional"))
      (node (ref "U$15") (pin "P$64") (pinfunction "P$2_P$64") (pintype "bidirectional"))
      (node (ref "U$15") (pin "P$65") (pinfunction "P$2_P$65") (pintype "bidirectional"))
      (node (ref "U$15") (pin "P$66") (pinfunction "P$2_P$66") (pintype "bidirectional"))
      (node (ref "U$15") (pin "P$67") (pinfunction "P$2_P$67") (pintype "bidirectional"))
      (node (ref "U$15") (pin "P$68") (pinfunction "P$2_P$68") (pintype "bidirectional"))
      (node (ref "U$15") (pin "P$69") (pinfunction "P$2_P$69") (pintype "bidirectional"))
      (node (ref "U$15") (pin "P$70") (pinfunction "P$2_P$70") (pintype "bidirectional"))
      (node (ref "U$15") (pin "P$71") (pinfunction "P$2_P$71") (pintype "bidirectional"))
      (node (ref "U$15") (pin "P$72") (pinfunction "P$2_P$72") (pintype "bidirectional"))
      (node (ref "U$15") (pin "P$73") (pinfunction "P$2_P$73") (pintype "bidirectional"))
      (node (ref "U$15") (pin "P$74") (pinfunction "P$2_P$74") (pintype "bidirectional"))
      (node (ref "U$15") (pin "P$75") (pinfunction "P$2_P$75") (pintype "bidirectional"))
      (node (ref "U$15") (pin "P$76") (pinfunction "P$2_P$76") (pintype "bidirectional"))
      (node (ref "U$15") (pin "P$77") (pinfunction "P$2_P$77") (pintype "bidirectional"))
      (node (ref "U$15") (pin "P$78") (pinfunction "P$2_P$78") (pintype "bidirectional"))
      (node (ref "U$15") (pin "P$79") (pinfunction "P$2_P$79") (pintype "bidirectional"))
      (node (ref "U$15") (pin "P$80") (pinfunction "P$2_P$80") (pintype "bidirectional"))
      (node (ref "U$15") (pin "P$81") (pinfunction "P$2_P$81") (pintype "bidirectional"))
      (node (ref "U$15") (pin "P$82") (pinfunction "P$2_P$82") (pintype "bidirectional"))
      (node (ref "U$15") (pin "P$83") (pinfunction "P$2_P$83") (pintype "bidirectional"))
      (node (ref "U$15") (pin "P$84") (pinfunction "P$2_P$84") (pintype "bidirectional"))
      (node (ref "U$15") (pin "P$85") (pinfunction "P$2_P$85") (pintype "bidirectional"))
      (node (ref "U$15") (pin "P$86") (pinfunction "P$2_P$86") (pintype "bidirectional"))
      (node (ref "U$15") (pin "P$87") (pinfunction "P$2_P$87") (pintype "bidirectional"))
      (node (ref "U$15") (pin "P$88") (pinfunction "P$2_P$88") (pintype "bidirectional"))
      (node (ref "U$15") (pin "P$89") (pinfunction "P$2_P$89") (pintype "bidirectional"))
      (node (ref "U$15") (pin "P$90") (pinfunction "P$2_P$90") (pintype "bidirectional"))
      (node (ref "U$15") (pin "P$91") (pinfunction "P$2_P$91") (pintype "bidirectional"))
      (node (ref "U$15") (pin "P$92") (pinfunction "P$2_P$92") (pintype "bidirectional"))
      (node (ref "U1") (pin "3") (pinfunction "S2_3") (pintype "bidirectional"))
      (node (ref "U3") (pin "3") (pinfunction "S2_3") (pintype "bidirectional"))
    )
    (net (code "3") (name "/48_I_ANALOG") (class "Default")
      (node (ref "U$15") (pin "P$8") (pinfunction "P$8_P$8") (pintype "bidirectional"))
      (node (ref "U$4") (pin "CH7") (pinfunction "CH7_CH7") (pintype "bidirectional"))
    )
    (net (code "4") (name "/CS") (class "Default")
      (node (ref "U$13") (pin "CS/SHDN") (pinfunction "CS/SHDN_CS/SHDN") (pintype "bidirectional"))
      (node (ref "U$4") (pin "CS/SHDN") (pinfunction "CS/SHDN_CS/SHDN") (pintype "bidirectional"))
      (node (ref "U2") (pin "14") (pinfunction "PB2(SS/OC1B)_14") (pintype "bidirectional"))
    )
    (net (code "5") (name "/CUR1") (class "Default")
      (node (ref "C1") (pin "2") (pinfunction "2_2") (pintype "passive"))
      (node (ref "U$1") (pin "VIOUT") (pinfunction "VIOUT_VIOUT") (pintype "bidirectional"))
      (node (ref "U$4") (pin "CH3") (pinfunction "CH3_CH3") (pintype "bidirectional"))
    )
    (net (code "6") (name "/CUR2") (class "Default")
      (node (ref "C2") (pin "2") (pinfunction "2_2") (pintype "passive"))
      (node (ref "U$2") (pin "VIOUT") (pinfunction "VIOUT_VIOUT") (pintype "bidirectional"))
      (node (ref "U$4") (pin "CH2") (pinfunction "CH2_CH2") (pintype "bidirectional"))
    )
    (net (code "7") (name "/CUR3") (class "Default")
      (node (ref "C3") (pin "2") (pinfunction "2_2") (pintype "passive"))
      (node (ref "U$13") (pin "CH5") (pinfunction "CH5_CH5") (pintype "bidirectional"))
      (node (ref "U$3") (pin "VIOUT") (pinfunction "VIOUT_VIOUT") (pintype "bidirectional"))
    )
    (net (code "8") (name "/CUR4") (class "Default")
      (node (ref "C62") (pin "2") (pinfunction "2_2") (pintype "passive"))
      (node (ref "U$13") (pin "CH4") (pinfunction "CH4_CH4") (pintype "bidirectional"))
      (node (ref "U$5") (pin "VIOUT") (pinfunction "VIOUT_VIOUT") (pintype "bidirectional"))
    )
    (net (code "9") (name "/CUR5") (class "Default")
      (node (ref "C63") (pin "2") (pinfunction "2_2") (pintype "passive"))
      (node (ref "U$4") (pin "CH4") (pinfunction "CH4_CH4") (pintype "bidirectional"))
      (node (ref "U$6") (pin "VIOUT") (pinfunction "VIOUT_VIOUT") (pintype "bidirectional"))
    )
    (net (code "10") (name "/CUR6") (class "Default")
      (node (ref "C64") (pin "2") (pinfunction "2_2") (pintype "passive"))
      (node (ref "U$4") (pin "CH1") (pinfunction "CH1_CH1") (pintype "bidirectional"))
      (node (ref "U$7") (pin "VIOUT") (pinfunction "VIOUT_VIOUT") (pintype "bidirectional"))
    )
    (net (code "11") (name "/CUR7") (class "Default")
      (node (ref "C65") (pin "2") (pinfunction "2_2") (pintype "passive"))
      (node (ref "U$13") (pin "CH6") (pinfunction "CH6_CH6") (pintype "bidirectional"))
      (node (ref "U$8") (pin "VIOUT") (pinfunction "VIOUT_VIOUT") (pintype "bidirectional"))
    )
    (net (code "12") (name "/CUR8") (class "Default")
      (node (ref "C66") (pin "2") (pinfunction "2_2") (pintype "passive"))
      (node (ref "U$13") (pin "CH3") (pinfunction "CH3_CH3") (pintype "bidirectional"))
      (node (ref "U$9") (pin "VIOUT") (pinfunction "VIOUT_VIOUT") (pintype "bidirectional"))
    )
    (net (code "13") (name "/CUR9") (class "Default")
      (node (ref "C67") (pin "2") (pinfunction "2_2") (pintype "passive"))
      (node (ref "U$10") (pin "VIOUT") (pinfunction "VIOUT_VIOUT") (pintype "bidirectional"))
      (node (ref "U$4") (pin "CH5") (pinfunction "CH5_CH5") (pintype "bidirectional"))
    )
    (net (code "14") (name "/CUR10") (class "Default")
      (node (ref "C68") (pin "2") (pinfunction "2_2") (pintype "passive"))
      (node (ref "U$11") (pin "VIOUT") (pinfunction "VIOUT_VIOUT") (pintype "bidirectional"))
      (node (ref "U$4") (pin "CH0") (pinfunction "CH0_CH0") (pintype "bidirectional"))
    )
    (net (code "15") (name "/CUR11") (class "Default")
      (node (ref "C69") (pin "2") (pinfunction "2_2") (pintype "passive"))
      (node (ref "U$12") (pin "VIOUT") (pinfunction "VIOUT_VIOUT") (pintype "bidirectional"))
      (node (ref "U$13") (pin "CH7") (pinfunction "CH7_CH7") (pintype "bidirectional"))
    )
    (net (code "16") (name "/E1") (class "Default")
      (node (ref "J5") (pin "2") (pinfunction "2_2") (pintype "passive"))
      (node (ref "U$4") (pin "CH6") (pinfunction "CH6_CH6") (pintype "bidirectional"))
    )
    (net (code "17") (name "/E3") (class "Default")
      (node (ref "J1") (pin "2") (pinfunction "2_2") (pintype "passive"))
      (node (ref "U$13") (pin "CH0") (pinfunction "CH0_CH0") (pintype "bidirectional"))
    )
    (net (code "18") (name "/E4") (class "Default")
      (node (ref "U$13") (pin "CH1") (pinfunction "CH1_CH1") (pintype "bidirectional"))
    )
    (net (code "19") (name "/ESC1") (class "Default")
      (node (ref "C18") (pin "+") (pinfunction "+_+") (pintype "passive"))
      (node (ref "C21") (pin "1") (pinfunction "1_1") (pintype "passive"))
      (node (ref "ESC1") (pin "VCC") (pinfunction "VCC_VCC") (pintype "bidirectional"))
      (node (ref "U$1") (pin "IP1-") (pinfunction "IP1-_IP1-") (pintype "bidirectional"))
      (node (ref "U$1") (pin "IP2-") (pinfunction "IP2-_IP2-") (pintype "bidirectional"))
    )
    (net (code "20") (name "/ESC2") (class "Default")
      (node (ref "C19") (pin "+") (pinfunction "+_+") (pintype "passive"))
      (node (ref "C22") (pin "1") (pinfunction "1_1") (pintype "passive"))
      (node (ref "ESC2") (pin "VCC") (pinfunction "VCC_VCC") (pintype "bidirectional"))
      (node (ref "U$2") (pin "IP1-") (pinfunction "IP1-_IP1-") (pintype "bidirectional"))
      (node (ref "U$2") (pin "IP2-") (pinfunction "IP2-_IP2-") (pintype "bidirectional"))
    )
    (net (code "21") (name "/ESC3") (class "Default")
      (node (ref "C20") (pin "+") (pinfunction "+_+") (pintype "passive"))
      (node (ref "C23") (pin "1") (pinfunction "1_1") (pintype "passive"))
      (node (ref "ESC3") (pin "VCC") (pinfunction "VCC_VCC") (pintype "bidirectional"))
      (node (ref "U$3") (pin "IP1-") (pinfunction "IP1-_IP1-") (pintype "bidirectional"))
      (node (ref "U$3") (pin "IP2-") (pinfunction "IP2-_IP2-") (pintype "bidirectional"))
    )
    (net (code "22") (name "/ESC4") (class "Default")
      (node (ref "C27") (pin "+") (pinfunction "+_+") (pintype "passive"))
      (node (ref "C30") (pin "1") (pinfunction "1_1") (pintype "passive"))
      (node (ref "ESC4") (pin "VCC") (pinfunction "VCC_VCC") (pintype "bidirectional"))
      (node (ref "U$5") (pin "IP1-") (pinfunction "IP1-_IP1-") (pintype "bidirectional"))
      (node (ref "U$5") (pin "IP2-") (pinfunction "IP2-_IP2-") (pintype "bidirectional"))
    )
    (net (code "23") (name "/ESC5") (class "Default")
      (node (ref "C28") (pin "+") (pinfunction "+_+") (pintype "passive"))
      (node (ref "C31") (pin "1") (pinfunction "1_1") (pintype "passive"))
      (node (ref "ESC5") (pin "VCC") (pinfunction "VCC_VCC") (pintype "bidirectional"))
      (node (ref "U$6") (pin "IP1-") (pinfunction "IP1-_IP1-") (pintype "bidirectional"))
      (node (ref "U$6") (pin "IP2-") (pinfunction "IP2-_IP2-") (pintype "bidirectional"))
    )
    (net (code "24") (name "/ESC6") (class "Default")
      (node (ref "C29") (pin "+") (pinfunction "+_+") (pintype "passive"))
      (node (ref "C32") (pin "1") (pinfunction "1_1") (pintype "passive"))
      (node (ref "ESC6") (pin "VCC") (pinfunction "VCC_VCC") (pintype "bidirectional"))
      (node (ref "U$7") (pin "IP1-") (pinfunction "IP1-_IP1-") (pintype "bidirectional"))
      (node (ref "U$7") (pin "IP2-") (pinfunction "IP2-_IP2-") (pintype "bidirectional"))
    )
    (net (code "25") (name "/ESC7") (class "Default")
      (node (ref "C33") (pin "+") (pinfunction "+_+") (pintype "passive"))
      (node (ref "C36") (pin "1") (pinfunction "1_1") (pintype "passive"))
      (node (ref "ESC7") (pin "VCC") (pinfunction "VCC_VCC") (pintype "bidirectional"))
      (node (ref "U$8") (pin "IP1-") (pinfunction "IP1-_IP1-") (pintype "bidirectional"))
      (node (ref "U$8") (pin "IP2-") (pinfunction "IP2-_IP2-") (pintype "bidirectional"))
    )
    (net (code "26") (name "/ESC8") (class "Default")
      (node (ref "C34") (pin "+") (pinfunction "+_+") (pintype "passive"))
      (node (ref "C37") (pin "1") (pinfunction "1_1") (pintype "passive"))
      (node (ref "ESC8") (pin "VCC") (pinfunction "VCC_VCC") (pintype "bidirectional"))
      (node (ref "U$9") (pin "IP1-") (pinfunction "IP1-_IP1-") (pintype "bidirectional"))
      (node (ref "U$9") (pin "IP2-") (pinfunction "IP2-_IP2-") (pintype "bidirectional"))
    )
    (net (code "27") (name "/ESC9") (class "Default")
      (node (ref "C35") (pin "+") (pinfunction "+_+") (pintype "passive"))
      (node (ref "C38") (pin "1") (pinfunction "1_1") (pintype "passive"))
      (node (ref "ESC9") (pin "VCC") (pinfunction "VCC_VCC") (pintype "bidirectional"))
      (node (ref "U$10") (pin "IP1-") (pinfunction "IP1-_IP1-") (pintype "bidirectional"))
      (node (ref "U$10") (pin "IP2-") (pinfunction "IP2-_IP2-") (pintype "bidirectional"))
    )
    (net (code "28") (name "/ESC10") (class "Default")
      (node (ref "C39") (pin "+") (pinfunction "+_+") (pintype "passive"))
      (node (ref "C42") (pin "1") (pinfunction "1_1") (pintype "passive"))
      (node (ref "ESC10") (pin "VCC") (pinfunction "VCC_VCC") (pintype "bidirectional"))
      (node (ref "U$11") (pin "IP1-") (pinfunction "IP1-_IP1-") (pintype "bidirectional"))
      (node (ref "U$11") (pin "IP2-") (pinfunction "IP2-_IP2-") (pintype "bidirectional"))
    )
    (net (code "29") (name "/ESC11") (class "Default")
      (node (ref "C40") (pin "+") (pinfunction "+_+") (pintype "passive"))
      (node (ref "C43") (pin "1") (pinfunction "1_1") (pintype "passive"))
      (node (ref "ESC11") (pin "VCC") (pinfunction "VCC_VCC") (pintype "bidirectional"))
      (node (ref "U$12") (pin "IP1-") (pinfunction "IP1-_IP1-") (pintype "bidirectional"))
      (node (ref "U$12") (pin "IP2-") (pinfunction "IP2-_IP2-") (pintype "bidirectional"))
    )
    (net (code "30") (name "/E_MAG_1") (class "Default")
      (node (ref "J4") (pin "2") (pinfunction "2_2") (pintype "passive"))
      (node (ref "R5") (pin "2") (pinfunction "2_2") (pintype "passive"))
      (node (ref "U1") (pin "TAB") (pinfunction "D2_TAB") (pintype "bidirectional"))
    )
    (net (code "31") (name "/E_MAG_1_ON") (class "Default")
      (node (ref "P6") (pin "1") (pinfunction "1_1") (pintype "passive"))
      (node (ref "U1") (pin "1") (pinfunction "G2_1") (pintype "bidirectional"))
      (node (ref "U4") (pin "12") (pinfunction "PWM6_12") (pintype "output"))
    )
    (net (code "32") (name "/E_MAG_2") (class "Default")
      (node (ref "J6") (pin "2") (pinfunction "2_2") (pintype "passive"))
      (node (ref "R4") (pin "2") (pinfunction "2_2") (pintype "passive"))
      (node (ref "U3") (pin "TAB") (pinfunction "D2_TAB") (pintype "bidirectional"))
    )
    (net (code "33") (name "/E_MAG_2_ON") (class "Default")
      (node (ref "P7") (pin "1") (pinfunction "1_1") (pintype "passive"))
      (node (ref "U3") (pin "1") (pinfunction "G2_1") (pintype "bidirectional"))
      (node (ref "U4") (pin "13") (pinfunction "PWM7_13") (pintype "output"))
    )
    (net (code "34") (name "/LED1") (class "Default")
      (node (ref "ESC7_CON1") (pin "B") (pinfunction "B_B") (pintype "bidirectional"))
      (node (ref "U4") (pin "15") (pinfunction "PWM8_15") (pintype "output"))
    )
    (net (code "35") (name "/LED2") (class "Default")
      (node (ref "ESC7_CON3") (pin "B") (pinfunction "B_B") (pintype "bidirectional"))
      (node (ref "U4") (pin "16") (pinfunction "PWM9_16") (pintype "output"))
    )
    (net (code "36") (name "/MISO") (class "Default")
      (node (ref "J3") (pin "1") (pinfunction "1_1") (pintype "passive"))
      (node (ref "U$13") (pin "DOUT") (pinfunction "DOUT_DOUT") (pintype "bidirectional"))
      (node (ref "U2") (pin "16") (pinfunction "PB4(MISO)_16") (pintype "bidirectional"))
    )
    (net (code "37") (name "/MOSI") (class "Default")
      (node (ref "J3") (pin "4") (pinfunction "4_4") (pintype "passive"))
      (node (ref "U$4") (pin "DIN") (pinfunction "DIN_DIN") (pintype "bidirectional"))
      (node (ref "U2") (pin "15") (pinfunction "PB3(MOSI/OC2)_15") (pintype "bidirectional"))
    )
    (net (code "38") (name "/OUT1") (class "Default")
      (node (ref "LED1") (pin "2-DOUT") (pinfunction "DO_2-DOUT") (pintype "output"))
      (node (ref "LED2") (pin "4-DIN") (pinfunction "DI_4-DIN") (pintype "input"))
    )
    (net (code "39") (name "/OUT2") (class "Default")
      (node (ref "LED2") (pin "2-DOUT") (pinfunction "DO_2-DOUT") (pintype "output"))
      (node (ref "LED3") (pin "4-DIN") (pinfunction "DI_4-DIN") (pintype "input"))
    )
    (net (code "40") (name "/OUT3") (class "Default")
      (node (ref "LED3") (pin "2-DOUT") (pinfunction "DO_2-DOUT") (pintype "output"))
      (node (ref "LED4") (pin "4-DIN") (pinfunction "DI_4-DIN") (pintype "input"))
    )
    (net (code "41") (name "/OUT4") (class "Default")
      (node (ref "LED4") (pin "2-DOUT") (pinfunction "DO_2-DOUT") (pintype "output"))
      (node (ref "LED5") (pin "4-DIN") (pinfunction "DI_4-DIN") (pintype "input"))
    )
    (net (code "42") (name "/OUT5") (class "Default")
      (node (ref "LED5") (pin "2-DOUT") (pinfunction "DO_2-DOUT") (pintype "output"))
      (node (ref "LED6") (pin "4-DIN") (pinfunction "DI_4-DIN") (pintype "input"))
    )
    (net (code "43") (name "/OUT6") (class "Default")
      (node (ref "LED6") (pin "2-DOUT") (pinfunction "DO_2-DOUT") (pintype "output"))
    )
    (net (code "44") (name "/PB0") (class "Default")
      (node (ref "U2") (pin "12") (pinfunction "PB0(ICP)_12") (pintype "bidirectional"))
    )
    (net (code "45") (name "/PD3") (class "Default")
      (node (ref "LED1") (pin "4-DIN") (pinfunction "DI_4-DIN") (pintype "input"))
      (node (ref "U2") (pin "1") (pinfunction "PD3(INT1)_1") (pintype "bidirectional"))
    )
    (net (code "46") (name "/PD4") (class "Default")
      (node (ref "U2") (pin "2") (pinfunction "PD4(XCK/T0)_2") (pintype "bidirectional"))
    )
    (net (code "47") (name "/PD5") (class "Default")
      (node (ref "U2") (pin "9") (pinfunction "PD5(T1)_9") (pintype "bidirectional"))
    )
    (net (code "48") (name "/PD6") (class "Default")
      (node (ref "U2") (pin "10") (pinfunction "PD6(AIN0)_10") (pintype "bidirectional"))
    )
    (net (code "49") (name "/PD7") (class "Default")
      (node (ref "U2") (pin "11") (pinfunction "PD7(AIN1)_11") (pintype "bidirectional"))
    )
    (net (code "50") (name "/PIEZO") (class "Default")
      (node (ref "ESC7_CON4") (pin "B") (pinfunction "B_B") (pintype "bidirectional"))
      (node (ref "U4") (pin "17") (pinfunction "PWM10_17") (pintype "output"))
    )
    (net (code "51") (name "/PWM1") (class "Default")
      (node (ref "ESC1") (pin "PWM_SGN") (pinfunction "PWM_SGN_PWM_SGN") (pintype "bidirectional"))
      (node (ref "P5") (pin "1") (pinfunction "1_1") (pintype "passive"))
      (node (ref "U4") (pin "11") (pinfunction "PWM5_11") (pintype "output"))
    )
    (net (code "52") (name "/PWM2") (class "Default")
      (node (ref "ESC2") (pin "PWM_SGN") (pinfunction "PWM_SGN_PWM_SGN") (pintype "bidirectional"))
      (node (ref "P4") (pin "1") (pinfunction "1_1") (pintype "passive"))
      (node (ref "U4") (pin "10") (pinfunction "PWM4_10") (pintype "output"))
    )
    (net (code "53") (name "/PWM3") (class "Default")
      (node (ref "ESC3") (pin "PWM_SGN") (pinfunction "PWM_SGN_PWM_SGN") (pintype "bidirectional"))
      (node (ref "P12") (pin "1") (pinfunction "1_1") (pintype "passive"))
      (node (ref "U4") (pin "19") (pinfunction "PWM12_19") (pintype "output"))
    )
    (net (code "54") (name "/PWM4") (class "Default")
      (node (ref "ESC4") (pin "PWM_SGN") (pinfunction "PWM_SGN_PWM_SGN") (pintype "bidirectional"))
      (node (ref "P11") (pin "1") (pinfunction "1_1") (pintype "passive"))
      (node (ref "U4") (pin "18") (pinfunction "PWM11_18") (pintype "output"))
    )
    (net (code "55") (name "/PWM5") (class "Default")
      (node (ref "ESC5") (pin "PWM_SGN") (pinfunction "PWM_SGN_PWM_SGN") (pintype "bidirectional"))
      (node (ref "P3") (pin "1") (pinfunction "1_1") (pintype "passive"))
      (node (ref "U4") (pin "9") (pinfunction "PWM3_9") (pintype "output"))
    )
    (net (code "56") (name "/PWM6") (class "Default")
      (node (ref "ESC6") (pin "PWM_SGN") (pinfunction "PWM_SGN_PWM_SGN") (pintype "bidirectional"))
      (node (ref "P2") (pin "1") (pinfunction "1_1") (pintype "passive"))
      (node (ref "U4") (pin "8") (pinfunction "PWM2_8") (pintype "output"))
    )
    (net (code "57") (name "/PWM7") (class "Default")
      (node (ref "ESC7") (pin "PWM_SGN") (pinfunction "PWM_SGN_PWM_SGN") (pintype "bidirectional"))
      (node (ref "P14") (pin "1") (pinfunction "1_1") (pintype "passive"))
      (node (ref "U4") (pin "21") (pinfunction "PWM14_21") (pintype "output"))
    )
    (net (code "58") (name "/PWM8") (class "Default")
      (node (ref "ESC8") (pin "PWM_SGN") (pinfunction "PWM_SGN_PWM_SGN") (pintype "bidirectional"))
      (node (ref "P13") (pin "1") (pinfunction "1_1") (pintype "passive"))
      (node (ref "U4") (pin "20") (pinfunction "PWM13_20") (pintype "output"))
    )
    (net (code "59") (name "/PWM9") (class "Default")
      (node (ref "ESC9") (pin "PWM_SGN") (pinfunction "PWM_SGN_PWM_SGN") (pintype "bidirectional"))
      (node (ref "P1") (pin "1") (pinfunction "1_1") (pintype "passive"))
      (node (ref "U4") (pin "7") (pinfunction "PWM1_7") (pintype "output"))
    )
    (net (code "60") (name "/PWM10") (class "Default")
      (node (ref "ESC10") (pin "PWM_SGN") (pinfunction "PWM_SGN_PWM_SGN") (pintype "bidirectional"))
      (node (ref "P16") (pin "1") (pinfunction "1_1") (pintype "passive"))
      (node (ref "U4") (pin "6") (pinfunction "PWM0_6") (pintype "output"))
    )
    (net (code "61") (name "/PWM11") (class "Default")
      (node (ref "ESC11") (pin "PWM_SGN") (pinfunction "PWM_SGN_PWM_SGN") (pintype "bidirectional"))
      (node (ref "P15") (pin "1") (pinfunction "1_1") (pintype "passive"))
      (node (ref "U4") (pin "22") (pinfunction "PWM15_22") (pintype "output"))
    )
    (net (code "62") (name "/RESET") (class "Default")
      (node (ref "C11") (pin "2") (pinfunction "2_2") (pintype "passive"))
      (node (ref "J3") (pin "5") (pinfunction "5_5") (pintype "passive"))
      (node (ref "R10") (pin "1") (pinfunction "1_1") (pintype "passive"))
      (node (ref "RESET") (pin "2") (pinfunction "P$2_2") (pintype "bidirectional"))
      (node (ref "U2") (pin "29") (pinfunction "PC6(/RESET)_29") (pintype "bidirectional"))
    )
    (net (code "63") (name "/SCK") (class "Default")
      (node (ref "J3") (pin "3") (pinfunction "3_3") (pintype "passive"))
      (node (ref "U$13") (pin "CLK") (pinfunction "CLK_CLK") (pintype "bidirectional"))
      (node (ref "U$4") (pin "CLK") (pinfunction "CLK_CLK") (pintype "bidirectional"))
      (node (ref "U2") (pin "17") (pinfunction "PB5(SCK)_17") (pintype "bidirectional"))
    )
    (net (code "64") (name "/SCL") (class "Default")
      (node (ref "U$15") (pin "P$1") (pinfunction "P$1_P$1") (pintype "bidirectional"))
      (node (ref "U2") (pin "28") (pinfunction "PC5(ADC5/SCL)_28") (pintype "bidirectional"))
      (node (ref "U4") (pin "26") (pinfunction "SCL_26") (pintype "bidirectional"))
    )
    (net (code "65") (name "/SDA") (class "Default")
      (node (ref "U$15") (pin "P$7") (pinfunction "P$7_P$7") (pintype "bidirectional"))
      (node (ref "U2") (pin "27") (pinfunction "PC4(ADC4/SDA)_27") (pintype "bidirectional"))
      (node (ref "U4") (pin "27") (pinfunction "SDA_27") (pintype "bidirectional"))
    )
    (net (code "66") (name "/TEMP1") (class "Default")
      (node (ref "U$13") (pin "DIN") (pinfunction "DIN_DIN") (pintype "bidirectional"))
      (node (ref "U$4") (pin "DOUT") (pinfunction "DOUT_DOUT") (pintype "bidirectional"))
    )
    (net (code "67") (name "/TEMP11") (class "Default")
      (node (ref "C56") (pin "1") (pinfunction "1_1") (pintype "passive"))
      (node (ref "R26") (pin "1") (pinfunction "1_1") (pintype "passive"))
      (node (ref "R27") (pin "2") (pinfunction "2_2") (pintype "passive"))
      (node (ref "U$13") (pin "CH2") (pinfunction "CH2_CH2") (pintype "bidirectional"))
    )
    (net (code "68") (name "GND") (class "Default")
      (node (ref "12V-TO-5V1") (pin "2") (pinfunction "GND_2") (pintype "power_in"))
      (node (ref "12V-TO-5V1") (pin "4") (pinfunction "TAB_4") (pintype "power_in"))
      (node (ref "C1") (pin "1") (pinfunction "1_1") (pintype "passive"))
      (node (ref "C10") (pin "2") (pinfunction "2_2") (pintype "passive"))
      (node (ref "C11") (pin "1") (pinfunction "1_1") (pintype "passive"))
      (node (ref "C12") (pin "2") (pinfunction "2_2") (pintype "passive"))
      (node (ref "C13") (pin "2") (pinfunction "2_2") (pintype "passive"))
      (node (ref "C14") (pin "2") (pinfunction "2_2") (pintype "passive"))
      (node (ref "C15") (pin "2") (pinfunction "2_2") (pintype "passive"))
      (node (ref "C16") (pin "2") (pinfunction "2_2") (pintype "passive"))
      (node (ref "C17") (pin "2") (pinfunction "2_2") (pintype "passive"))
      (node (ref "C18") (pin "-") (pinfunction "-_-") (pintype "passive"))
      (node (ref "C19") (pin "-") (pinfunction "-_-") (pintype "passive"))
      (node (ref "C2") (pin "1") (pinfunction "1_1") (pintype "passive"))
      (node (ref "C20") (pin "-") (pinfunction "-_-") (pintype "passive"))
      (node (ref "C21") (pin "2") (pinfunction "2_2") (pintype "passive"))
      (node (ref "C22") (pin "2") (pinfunction "2_2") (pintype "passive"))
      (node (ref "C23") (pin "2") (pinfunction "2_2") (pintype "passive"))
      (node (ref "C24") (pin "1") (pinfunction "1_1") (pintype "passive"))
      (node (ref "C25") (pin "1") (pinfunction "1_1") (pintype "passive"))
      (node (ref "C26") (pin "1") (pinfunction "1_1") (pintype "passive"))
      (node (ref "C27") (pin "-") (pinfunction "-_-") (pintype "passive"))
      (node (ref "C28") (pin "-") (pinfunction "-_-") (pintype "passive"))
      (node (ref "C29") (pin "-") (pinfunction "-_-") (pintype "passive"))
      (node (ref "C3") (pin "1") (pinfunction "1_1") (pintype "passive"))
      (node (ref "C30") (pin "2") (pinfunction "2_2") (pintype "passive"))
      (node (ref "C31") (pin "2") (pinfunction "2_2") (pintype "passive"))
      (node (ref "C32") (pin "2") (pinfunction "2_2") (pintype "passive"))
      (node (ref "C33") (pin "-") (pinfunction "-_-") (pintype "passive"))
      (node (ref "C34") (pin "-") (pinfunction "-_-") (pintype "passive"))
      (node (ref "C35") (pin "-") (pinfunction "-_-") (pintype "passive"))
      (node (ref "C36") (pin "2") (pinfunction "2_2") (pintype "passive"))
      (node (ref "C37") (pin "2") (pinfunction "2_2") (pintype "passive"))
      (node (ref "C38") (pin "2") (pinfunction "2_2") (pintype "passive"))
      (node (ref "C39") (pin "-") (pinfunction "-_-") (pintype "passive"))
      (node (ref "C4") (pin "2") (pinfunction "2_2") (pintype "passive"))
      (node (ref "C40") (pin "-") (pinfunction "-_-") (pintype "passive"))
      (node (ref "C41") (pin "2") (pinfunction "2_2") (pintype "passive"))
      (node (ref "C42") (pin "2") (pinfunction "2_2") (pintype "passive"))
      (node (ref "C43") (pin "2") (pinfunction "2_2") (pintype "passive"))
      (node (ref "C44") (pin "2") (pinfunction "2_2") (pintype "passive"))
      (node (ref "C45") (pin "2") (pinfunction "2_2") (pintype "passive"))
      (node (ref "C46") (pin "2") (pinfunction "2_2") (pintype "passive"))
      (node (ref "C47") (pin "2") (pinfunction "2_2") (pintype "passive"))
      (node (ref "C48") (pin "2") (pinfunction "2_2") (pintype "passive"))
      (node (ref "C49") (pin "2") (pinfunction "2_2") (pintype "passive"))
      (node (ref "C5") (pin "2") (pinfunction "2_2") (pintype "passive"))
      (node (ref "C50") (pin "2") (pinfunction "2_2") (pintype "passive"))
      (node (ref "C51") (pin "2") (pinfunction "2_2") (pintype "passive"))
      (node (ref "C52") (pin "2") (pinfunction "2_2") (pintype "passive"))
      (node (ref "C56") (pin "2") (pinfunction "2_2") (pintype "passive"))
      (node (ref "C6") (pin "2") (pinfunction "2_2") (pintype "passive"))
      (node (ref "C62") (pin "1") (pinfunction "1_1") (pintype "passive"))
      (node (ref "C63") (pin "1") (pinfunction "1_1") (pintype "passive"))
      (node (ref "C64") (pin "1") (pinfunction "1_1") (pintype "passive"))
      (node (ref "C65") (pin "1") (pinfunction "1_1") (pintype "passive"))
      (node (ref "C66") (pin "1") (pinfunction "1_1") (pintype "passive"))
      (node (ref "C67") (pin "1") (pinfunction "1_1") (pintype "passive"))
      (node (ref "C68") (pin "1") (pinfunction "1_1") (pintype "passive"))
      (node (ref "C69") (pin "1") (pinfunction "1_1") (pintype "passive"))
      (node (ref "C70") (pin "2") (pinfunction "2_2") (pintype "passive"))
      (node (ref "C71") (pin "2") (pinfunction "2_2") (pintype "passive"))
      (node (ref "C72") (pin "2") (pinfunction "2_2") (pintype "passive"))
      (node (ref "C73") (pin "2") (pinfunction "2_2") (pintype "passive"))
      (node (ref "C74") (pin "2") (pinfunction "2_2") (pintype "passive"))
      (node (ref "C75") (pin "2") (pinfunction "2_2") (pintype "passive"))
      (node (ref "ESC1") (pin "GND") (pinfunction "GND_GND") (pintype "bidirectional"))
      (node (ref "ESC1") (pin "PWM_GND") (pinfunction "PWM_GND_PWM_GND") (pintype "bidirectional"))
      (node (ref "ESC10") (pin "GND") (pinfunction "GND_GND") (pintype "bidirectional"))
      (node (ref "ESC10") (pin "PWM_GND") (pinfunction "PWM_GND_PWM_GND") (pintype "bidirectional"))
      (node (ref "ESC11") (pin "GND") (pinfunction "GND_GND") (pintype "bidirectional"))
      (node (ref "ESC11") (pin "PWM_GND") (pinfunction "PWM_GND_PWM_GND") (pintype "bidirectional"))
      (node (ref "ESC2") (pin "GND") (pinfunction "GND_GND") (pintype "bidirectional"))
      (node (ref "ESC2") (pin "PWM_GND") (pinfunction "PWM_GND_PWM_GND") (pintype "bidirectional"))
      (node (ref "ESC3") (pin "GND") (pinfunction "GND_GND") (pintype "bidirectional"))
      (node (ref "ESC3") (pin "PWM_GND") (pinfunction "PWM_GND_PWM_GND") (pintype "bidirectional"))
      (node (ref "ESC4") (pin "GND") (pinfunction "GND_GND") (pintype "bidirectional"))
      (node (ref "ESC4") (pin "PWM_GND") (pinfunction "PWM_GND_PWM_GND") (pintype "bidirectional"))
      (node (ref "ESC5") (pin "GND") (pinfunction "GND_GND") (pintype "bidirectional"))
      (node (ref "ESC5") (pin "PWM_GND") (pinfunction "PWM_GND_PWM_GND") (pintype "bidirectional"))
      (node (ref "ESC6") (pin "GND") (pinfunction "GND_GND") (pintype "bidirectional"))
      (node (ref "ESC6") (pin "PWM_GND") (pinfunction "PWM_GND_PWM_GND") (pintype "bidirectional"))
      (node (ref "ESC7") (pin "GND") (pinfunction "GND_GND") (pintype "bidirectional"))
      (node (ref "ESC7") (pin "PWM_GND") (pinfunction "PWM_GND_PWM_GND") (pintype "bidirectional"))
      (node (ref "ESC7_CON1") (pin "A") (pinfunction "A_A") (pintype "bidirectional"))
      (node (ref "ESC7_CON3") (pin "A") (pinfunction "A_A") (pintype "bidirectional"))
      (node (ref "ESC7_CON4") (pin "A") (pinfunction "A_A") (pintype "bidirectional"))
      (node (ref "ESC8") (pin "GND") (pinfunction "GND_GND") (pintype "bidirectional"))
      (node (ref "ESC8") (pin "PWM_GND") (pinfunction "PWM_GND_PWM_GND") (pintype "bidirectional"))
      (node (ref "ESC9") (pin "GND") (pinfunction "GND_GND") (pintype "bidirectional"))
      (node (ref "ESC9") (pin "PWM_GND") (pinfunction "PWM_GND_PWM_GND") (pintype "bidirectional"))
      (node (ref "J1") (pin "1") (pinfunction "1_1") (pintype "passive"))
      (node (ref "J3") (pin "6") (pinfunction "6_6") (pintype "passive"))
      (node (ref "J4") (pin "1") (pinfunction "1_1") (pintype "passive"))
      (node (ref "J5") (pin "1") (pinfunction "1_1") (pintype "passive"))
      (node (ref "J6") (pin "1") (pinfunction "1_1") (pintype "passive"))
      (node (ref "J7") (pin "P$1") (pinfunction "1_P$1") (pintype "passive"))
      (node (ref "LED1") (pin "3-GND") (pinfunction "GND_3-GND") (pintype "power_in"))
      (node (ref "LED10") (pin "C") (pinfunction "C_C") (pintype "passive"))
      (node (ref "LED2") (pin "3-GND") (pinfunction "GND_3-GND") (pintype "power_in"))
      (node (ref "LED3") (pin "3-GND") (pinfunction "GND_3-GND") (pintype "power_in"))
      (node (ref "LED4") (pin "3-GND") (pinfunction "GND_3-GND") (pintype "power_in"))
      (node (ref "LED5") (pin "3-GND") (pinfunction "GND_3-GND") (pintype "power_in"))
      (node (ref "LED6") (pin "3-GND") (pinfunction "GND_3-GND") (pintype "power_in"))
      (node (ref "LED9") (pin "C") (pinfunction "C_C") (pintype "passive"))
      (node (ref "R19") (pin "1") (pinfunction "1_1") (pintype "passive"))
      (node (ref "R27") (pin "1") (pinfunction "1_1") (pintype "passive"))
      (node (ref "RESET") (pin "1") (pinfunction "P$1_1") (pintype "bidirectional"))
      (node (ref "U$1") (pin "GND") (pinfunction "GND_GND") (pintype "bidirectional"))
      (node (ref "U$10") (pin "GND") (pinfunction "GND_GND") (pintype "bidirectional"))
      (node (ref "U$11") (pin "GND") (pinfunction "GND_GND") (pintype "bidirectional"))
      (node (ref "U$12") (pin "GND") (pinfunction "GND_GND") (pintype "bidirectional"))
      (node (ref "U$13") (pin "AGND") (pinfunction "AGND_AGND") (pintype "bidirectional"))
      (node (ref "U$13") (pin "DGND") (pinfunction "DGND_DGND") (pintype "bidirectional"))
      (node (ref "U$15") (pin "P$10") (pinfunction "P$10_P$10") (pintype "bidirectional"))
      (node (ref "U$15") (pin "P$11") (pinfunction "P$11_P$11") (pintype "bidirectional"))
      (node (ref "U$15") (pin "P$12") (pinfunction "P$12_P$12") (pintype "bidirectional"))
      (node (ref "U$15") (pin "P$13") (pinfunction "P$1_P$13") (pintype "bidirectional"))
      (node (ref "U$15") (pin "P$14") (pinfunction "P$1_P$14") (pintype "bidirectional"))
      (node (ref "U$15") (pin "P$15") (pinfunction "P$1_P$15") (pintype "bidirectional"))
      (node (ref "U$15") (pin "P$16") (pinfunction "P$1_P$16") (pintype "bidirectional"))
      (node (ref "U$15") (pin "P$17") (pinfunction "P$1_P$17") (pintype "bidirectional"))
      (node (ref "U$15") (pin "P$18") (pinfunction "P$1_P$18") (pintype "bidirectional"))
      (node (ref "U$15") (pin "P$19") (pinfunction "P$1_P$19") (pintype "bidirectional"))
      (node (ref "U$15") (pin "P$20") (pinfunction "P$1_P$20") (pintype "bidirectional"))
      (node (ref "U$15") (pin "P$21") (pinfunction "P$1_P$21") (pintype "bidirectional"))
      (node (ref "U$15") (pin "P$22") (pinfunction "P$1_P$22") (pintype "bidirectional"))
      (node (ref "U$15") (pin "P$23") (pinfunction "P$1_P$23") (pintype "bidirectional"))
      (node (ref "U$15") (pin "P$24") (pinfunction "P$1_P$24") (pintype "bidirectional"))
      (node (ref "U$15") (pin "P$25") (pinfunction "P$1_P$25") (pintype "bidirectional"))
      (node (ref "U$15") (pin "P$26") (pinfunction "P$1_P$26") (pintype "bidirectional"))
      (node (ref "U$15") (pin "P$27") (pinfunction "P$1_P$27") (pintype "bidirectional"))
      (node (ref "U$15") (pin "P$28") (pinfunction "P$1_P$28") (pintype "bidirectional"))
      (node (ref "U$15") (pin "P$29") (pinfunction "P$1_P$29") (pintype "bidirectional"))
      (node (ref "U$15") (pin "P$30") (pinfunction "P$1_P$30") (pintype "bidirectional"))
      (node (ref "U$15") (pin "P$31") (pinfunction "P$1_P$31") (pintype "bidirectional"))
      (node (ref "U$15") (pin "P$32") (pinfunction "P$1_P$32") (pintype "bidirectional"))
      (node (ref "U$15") (pin "P$33") (pinfunction "P$1_P$33") (pintype "bidirectional"))
      (node (ref "U$15") (pin "P$34") (pinfunction "P$1_P$34") (pintype "bidirectional"))
      (node (ref "U$15") (pin "P$35") (pinfunction "P$1_P$35") (pintype "bidirectional"))
      (node (ref "U$15") (pin "P$36") (pinfunction "P$1_P$36") (pintype "bidirectional"))
      (node (ref "U$15") (pin "P$37") (pinfunction "P$1_P$37") (pintype "bidirectional"))
      (node (ref "U$15") (pin "P$38") (pinfunction "P$1_P$38") (pintype "bidirectional"))
      (node (ref "U$15") (pin "P$39") (pinfunction "P$1_P$39") (pintype "bidirectional"))
      (node (ref "U$15") (pin "P$40") (pinfunction "P$1_P$40") (pintype "bidirectional"))
      (node (ref "U$15") (pin "P$41") (pinfunction "P$1_P$41") (pintype "bidirectional"))
      (node (ref "U$15") (pin "P$42") (pinfunction "P$1_P$42") (pintype "bidirectional"))
      (node (ref "U$15") (pin "P$43") (pinfunction "P$1_P$43") (pintype "bidirectional"))
      (node (ref "U$15") (pin "P$44") (pinfunction "P$1_P$44") (pintype "bidirectional"))
      (node (ref "U$15") (pin "P$45") (pinfunction "P$1_P$45") (pintype "bidirectional"))
      (node (ref "U$15") (pin "P$46") (pinfunction "P$1_P$46") (pintype "bidirectional"))
      (node (ref "U$15") (pin "P$47") (pinfunction "P$1_P$47") (pintype "bidirectional"))
      (node (ref "U$15") (pin "P$48") (pinfunction "P$1_P$48") (pintype "bidirectional"))
      (node (ref "U$15") (pin "P$49") (pinfunction "P$1_P$49") (pintype "bidirectional"))
      (node (ref "U$15") (pin "P$50") (pinfunction "P$1_P$50") (pintype "bidirectional"))
      (node (ref "U$15") (pin "P$51") (pinfunction "P$1_P$51") (pintype "bidirectional"))
      (node (ref "U$15") (pin "P$52") (pinfunction "P$1_P$52") (pintype "bidirectional"))
      (node (ref "U$15") (pin "P$53") (pinfunction "P$1_P$53") (pintype "bidirectional"))
      (node (ref "U$15") (pin "P$54") (pinfunction "P$1_P$54") (pintype "bidirectional"))
      (node (ref "U$15") (pin "P$55") (pinfunction "P$1_P$55") (pintype "bidirectional"))
      (node (ref "U$15") (pin "P$56") (pinfunction "P$1_P$56") (pintype "bidirectional"))
      (node (ref "U$15") (pin "P$57") (pinfunction "P$1_P$57") (pintype "bidirectional"))
      (node (ref "U$15") (pin "P$58") (pinfunction "P$1_P$58") (pintype "bidirectional"))
      (node (ref "U$15") (pin "P$59") (pinfunction "P$1_P$59") (pintype "bidirectional"))
      (node (ref "U$15") (pin "P$60") (pinfunction "P$1_P$60") (pintype "bidirectional"))
      (node (ref "U$15") (pin "P$61") (pinfunction "P$1_P$61") (pintype "bidirectional"))
      (node (ref "U$15") (pin "P$62") (pinfunction "P$1_P$62") (pintype "bidirectional"))
      (node (ref "U$2") (pin "GND") (pinfunction "GND_GND") (pintype "bidirectional"))
      (node (ref "U$3") (pin "GND") (pinfunction "GND_GND") (pintype "bidirectional"))
      (node (ref "U$4") (pin "AGND") (pinfunction "AGND_AGND") (pintype "bidirectional"))
      (node (ref "U$4") (pin "DGND") (pinfunction "DGND_DGND") (pintype "bidirectional"))
      (node (ref "U$5") (pin "GND") (pinfunction "GND_GND") (pintype "bidirectional"))
      (node (ref "U$6") (pin "GND") (pinfunction "GND_GND") (pintype "bidirectional"))
      (node (ref "U$7") (pin "GND") (pinfunction "GND_GND") (pintype "bidirectional"))
      (node (ref "U$8") (pin "GND") (pinfunction "GND_GND") (pintype "bidirectional"))
      (node (ref "U$9") (pin "GND") (pinfunction "GND_GND") (pintype "bidirectional"))
      (node (ref "U2") (pin "21") (pinfunction "AGND_21") (pintype "bidirectional"))
      (node (ref "U2") (pin "3") (pinfunction "GND_3") (pintype "bidirectional"))
      (node (ref "U2") (pin "5") (pinfunction "GND_5") (pintype "bidirectional"))
      (node (ref "U4") (pin "1") (pinfunction "A0_1") (pintype "bidirectional"))
      (node (ref "U4") (pin "14") (pinfunction "GND_14") (pintype "power_in"))
      (node (ref "U4") (pin "2") (pinfunction "A1_2") (pintype "bidirectional"))
      (node (ref "U4") (pin "24") (pinfunction "A5_24") (pintype "bidirectional"))
      (node (ref "U4") (pin "25") (pinfunction "EXTCLK_25") (pintype "input"))
      (node (ref "U4") (pin "3") (pinfunction "A2_3") (pintype "bidirectional"))
      (node (ref "U4") (pin "4") (pinfunction "A3_4") (pintype "bidirectional"))
      (node (ref "U4") (pin "5") (pinfunction "A4_5") (pintype "bidirectional"))
    )
    (net (code "69") (name "Net-(ESC1-PadBLK)") (class "Default")
      (node (ref "ESC1") (pin "BLK") (pinfunction "BLK_BLK") (pintype "bidirectional"))
      (node (ref "ESC1_CON") (pin "A") (pinfunction "A_A") (pintype "bidirectional"))
    )
    (net (code "70") (name "Net-(ESC1-PadRED)") (class "Default")
      (node (ref "ESC1") (pin "RED") (pinfunction "RED_RED") (pintype "bidirectional"))
      (node (ref "ESC1_CON") (pin "C") (pinfunction "C_C") (pintype "bidirectional"))
    )
    (net (code "71") (name "Net-(ESC1-PadYEL)") (class "Default")
      (node (ref "ESC1") (pin "YEL") (pinfunction "YEL_YEL") (pintype "bidirectional"))
      (node (ref "ESC1_CON") (pin "B") (pinfunction "B_B") (pintype "bidirectional"))
    )
    (net (code "72") (name "Net-(ESC2-PadBLK)") (class "Default")
      (node (ref "ESC2") (pin "BLK") (pinfunction "BLK_BLK") (pintype "bidirectional"))
      (node (ref "ESC2_CON") (pin "A") (pinfunction "A_A") (pintype "bidirectional"))
    )
    (net (code "73") (name "Net-(ESC2-PadRED)") (class "Default")
      (node (ref "ESC2") (pin "RED") (pinfunction "RED_RED") (pintype "bidirectional"))
      (node (ref "ESC2_CON") (pin "C") (pinfunction "C_C") (pintype "bidirectional"))
    )
    (net (code "74") (name "Net-(ESC2-PadYEL)") (class "Default")
      (node (ref "ESC2") (pin "YEL") (pinfunction "YEL_YEL") (pintype "bidirectional"))
      (node (ref "ESC2_CON") (pin "B") (pinfunction "B_B") (pintype "bidirectional"))
    )
    (net (code "75") (name "Net-(ESC3-PadBLK)") (class "Default")
      (node (ref "ESC3") (pin "BLK") (pinfunction "BLK_BLK") (pintype "bidirectional"))
      (node (ref "ESC3_CON") (pin "A") (pinfunction "A_A") (pintype "bidirectional"))
    )
    (net (code "76") (name "Net-(ESC3-PadRED)") (class "Default")
      (node (ref "ESC3") (pin "RED") (pinfunction "RED_RED") (pintype "bidirectional"))
      (node (ref "ESC3_CON") (pin "C") (pinfunction "C_C") (pintype "bidirectional"))
    )
    (net (code "77") (name "Net-(ESC3-PadYEL)") (class "Default")
      (node (ref "ESC3") (pin "YEL") (pinfunction "YEL_YEL") (pintype "bidirectional"))
      (node (ref "ESC3_CON") (pin "B") (pinfunction "B_B") (pintype "bidirectional"))
    )
    (net (code "78") (name "Net-(ESC4-PadBLK)") (class "Default")
      (node (ref "ESC4") (pin "BLK") (pinfunction "BLK_BLK") (pintype "bidirectional"))
      (node (ref "ESC4_CON1") (pin "A") (pinfunction "A_A") (pintype "bidirectional"))
    )
    (net (code "79") (name "Net-(ESC4-PadRED)") (class "Default")
      (node (ref "ESC4") (pin "RED") (pinfunction "RED_RED") (pintype "bidirectional"))
      (node (ref "ESC4_CON1") (pin "C") (pinfunction "C_C") (pintype "bidirectional"))
    )
    (net (code "80") (name "Net-(ESC4-PadYEL)") (class "Default")
      (node (ref "ESC4") (pin "YEL") (pinfunction "YEL_YEL") (pintype "bidirectional"))
      (node (ref "ESC4_CON1") (pin "B") (pinfunction "B_B") (pintype "bidirectional"))
    )
    (net (code "81") (name "Net-(ESC5-PadBLK)") (class "Default")
      (node (ref "ESC5") (pin "BLK") (pinfunction "BLK_BLK") (pintype "bidirectional"))
      (node (ref "ESC5_CON1") (pin "A") (pinfunction "A_A") (pintype "bidirectional"))
    )
    (net (code "82") (name "Net-(ESC5-PadRED)") (class "Default")
      (node (ref "ESC5") (pin "RED") (pinfunction "RED_RED") (pintype "bidirectional"))
      (node (ref "ESC5_CON1") (pin "C") (pinfunction "C_C") (pintype "bidirectional"))
    )
    (net (code "83") (name "Net-(ESC5-PadYEL)") (class "Default")
      (node (ref "ESC5") (pin "YEL") (pinfunction "YEL_YEL") (pintype "bidirectional"))
      (node (ref "ESC5_CON1") (pin "B") (pinfunction "B_B") (pintype "bidirectional"))
    )
    (net (code "84") (name "Net-(ESC6-PadBLK)") (class "Default")
      (node (ref "ESC6") (pin "BLK") (pinfunction "BLK_BLK") (pintype "bidirectional"))
      (node (ref "ESC6_CON1") (pin "A") (pinfunction "A_A") (pintype "bidirectional"))
    )
    (net (code "85") (name "Net-(ESC6-PadRED)") (class "Default")
      (node (ref "ESC6") (pin "RED") (pinfunction "RED_RED") (pintype "bidirectional"))
      (node (ref "ESC6_CON1") (pin "C") (pinfunction "C_C") (pintype "bidirectional"))
    )
    (net (code "86") (name "Net-(ESC6-PadYEL)") (class "Default")
      (node (ref "ESC6") (pin "YEL") (pinfunction "YEL_YEL") (pintype "bidirectional"))
      (node (ref "ESC6_CON1") (pin "B") (pinfunction "B_B") (pintype "bidirectional"))
    )
    (net (code "87") (name "Net-(ESC7-PadBLK)") (class "Default")
      (node (ref "ESC7") (pin "BLK") (pinfunction "BLK_BLK") (pintype "bidirectional"))
      (node (ref "ESC7_CON2") (pin "A") (pinfunction "A_A") (pintype "bidirectional"))
    )
    (net (code "88") (name "Net-(ESC7-PadRED)") (class "Default")
      (node (ref "ESC7") (pin "RED") (pinfunction "RED_RED") (pintype "bidirectional"))
      (node (ref "ESC7_CON2") (pin "C") (pinfunction "C_C") (pintype "bidirectional"))
    )
    (net (code "89") (name "Net-(ESC7-PadYEL)") (class "Default")
      (node (ref "ESC7") (pin "YEL") (pinfunction "YEL_YEL") (pintype "bidirectional"))
      (node (ref "ESC7_CON2") (pin "B") (pinfunction "B_B") (pintype "bidirectional"))
    )
    (net (code "90") (name "Net-(ESC8-PadBLK)") (class "Default")
      (node (ref "ESC8") (pin "BLK") (pinfunction "BLK_BLK") (pintype "bidirectional"))
      (node (ref "ESC8_CON2") (pin "A") (pinfunction "A_A") (pintype "bidirectional"))
    )
    (net (code "91") (name "Net-(ESC8-PadRED)") (class "Default")
      (node (ref "ESC8") (pin "RED") (pinfunction "RED_RED") (pintype "bidirectional"))
      (node (ref "ESC8_CON2") (pin "C") (pinfunction "C_C") (pintype "bidirectional"))
    )
    (net (code "92") (name "Net-(ESC8-PadYEL)") (class "Default")
      (node (ref "ESC8") (pin "YEL") (pinfunction "YEL_YEL") (pintype "bidirectional"))
      (node (ref "ESC8_CON2") (pin "B") (pinfunction "B_B") (pintype "bidirectional"))
    )
    (net (code "93") (name "Net-(ESC9-PadBLK)") (class "Default")
      (node (ref "ESC9") (pin "BLK") (pinfunction "BLK_BLK") (pintype "bidirectional"))
      (node (ref "ESC9_CON2") (pin "A") (pinfunction "A_A") (pintype "bidirectional"))
    )
    (net (code "94") (name "Net-(ESC9-PadRED)") (class "Default")
      (node (ref "ESC9") (pin "RED") (pinfunction "RED_RED") (pintype "bidirectional"))
      (node (ref "ESC9_CON2") (pin "C") (pinfunction "C_C") (pintype "bidirectional"))
    )
    (net (code "95") (name "Net-(ESC9-PadYEL)") (class "Default")
      (node (ref "ESC9") (pin "YEL") (pinfunction "YEL_YEL") (pintype "bidirectional"))
      (node (ref "ESC9_CON2") (pin "B") (pinfunction "B_B") (pintype "bidirectional"))
    )
    (net (code "96") (name "Net-(ESC10-PadBLK)") (class "Default")
      (node (ref "ESC10") (pin "BLK") (pinfunction "BLK_BLK") (pintype "bidirectional"))
      (node (ref "ESC10_CON3") (pin "A") (pinfunction "A_A") (pintype "bidirectional"))
    )
    (net (code "97") (name "Net-(ESC10-PadRED)") (class "Default")
      (node (ref "ESC10") (pin "RED") (pinfunction "RED_RED") (pintype "bidirectional"))
      (node (ref "ESC10_CON3") (pin "C") (pinfunction "C_C") (pintype "bidirectional"))
    )
    (net (code "98") (name "Net-(ESC10-PadYEL)") (class "Default")
      (node (ref "ESC10") (pin "YEL") (pinfunction "YEL_YEL") (pintype "bidirectional"))
      (node (ref "ESC10_CON3") (pin "B") (pinfunction "B_B") (pintype "bidirectional"))
    )
    (net (code "99") (name "Net-(ESC11-PadBLK)") (class "Default")
      (node (ref "ESC11") (pin "BLK") (pinfunction "BLK_BLK") (pintype "bidirectional"))
      (node (ref "ESC11_CON3") (pin "A") (pinfunction "A_A") (pintype "bidirectional"))
    )
    (net (code "100") (name "Net-(ESC11-PadRED)") (class "Default")
      (node (ref "ESC11") (pin "RED") (pinfunction "RED_RED") (pintype "bidirectional"))
      (node (ref "ESC11_CON3") (pin "C") (pinfunction "C_C") (pintype "bidirectional"))
    )
    (net (code "101") (name "Net-(ESC11-PadYEL)") (class "Default")
      (node (ref "ESC11") (pin "YEL") (pinfunction "YEL_YEL") (pintype "bidirectional"))
      (node (ref "ESC11_CON3") (pin "B") (pinfunction "B_B") (pintype "bidirectional"))
    )
    (net (code "102") (name "Net-(F1-Pad1)") (class "Default")
      (node (ref "F1") (pin "1") (pinfunction "1_1") (pintype "bidirectional"))
      (node (ref "U$1") (pin "IP1+") (pinfunction "IP1+_IP1+") (pintype "bidirectional"))
      (node (ref "U$1") (pin "IP2+") (pinfunction "IP2+_IP2+") (pintype "bidirectional"))
    )
    (net (code "103") (name "Net-(F2-Pad1)") (class "Default")
      (node (ref "F2") (pin "1") (pinfunction "1_1") (pintype "bidirectional"))
      (node (ref "U$2") (pin "IP1+") (pinfunction "IP1+_IP1+") (pintype "bidirectional"))
      (node (ref "U$2") (pin "IP2+") (pinfunction "IP2+_IP2+") (pintype "bidirectional"))
    )
    (net (code "104") (name "Net-(F3-Pad1)") (class "Default")
      (node (ref "F3") (pin "1") (pinfunction "1_1") (pintype "bidirectional"))
      (node (ref "U$3") (pin "IP1+") (pinfunction "IP1+_IP1+") (pintype "bidirectional"))
      (node (ref "U$3") (pin "IP2+") (pinfunction "IP2+_IP2+") (pintype "bidirectional"))
    )
    (net (code "105") (name "Net-(F4-Pad1)") (class "Default")
      (node (ref "F4") (pin "1") (pinfunction "1_1") (pintype "bidirectional"))
      (node (ref "U$5") (pin "IP1+") (pinfunction "IP1+_IP1+") (pintype "bidirectional"))
      (node (ref "U$5") (pin "IP2+") (pinfunction "IP2+_IP2+") (pintype "bidirectional"))
    )
    (net (code "106") (name "Net-(F5-Pad1)") (class "Default")
      (node (ref "F5") (pin "1") (pinfunction "1_1") (pintype "bidirectional"))
      (node (ref "U$6") (pin "IP1+") (pinfunction "IP1+_IP1+") (pintype "bidirectional"))
      (node (ref "U$6") (pin "IP2+") (pinfunction "IP2+_IP2+") (pintype "bidirectional"))
    )
    (net (code "107") (name "Net-(F6-Pad1)") (class "Default")
      (node (ref "F6") (pin "1") (pinfunction "1_1") (pintype "bidirectional"))
      (node (ref "U$7") (pin "IP1+") (pinfunction "IP1+_IP1+") (pintype "bidirectional"))
      (node (ref "U$7") (pin "IP2+") (pinfunction "IP2+_IP2+") (pintype "bidirectional"))
    )
    (net (code "108") (name "Net-(F7-Pad1)") (class "Default")
      (node (ref "F7") (pin "1") (pinfunction "1_1") (pintype "bidirectional"))
      (node (ref "U$8") (pin "IP1+") (pinfunction "IP1+_IP1+") (pintype "bidirectional"))
      (node (ref "U$8") (pin "IP2+") (pinfunction "IP2+_IP2+") (pintype "bidirectional"))
    )
    (net (code "109") (name "Net-(F8-Pad1)") (class "Default")
      (node (ref "F8") (pin "1") (pinfunction "1_1") (pintype "bidirectional"))
      (node (ref "U$9") (pin "IP1+") (pinfunction "IP1+_IP1+") (pintype "bidirectional"))
      (node (ref "U$9") (pin "IP2+") (pinfunction "IP2+_IP2+") (pintype "bidirectional"))
    )
    (net (code "110") (name "Net-(F9-Pad1)") (class "Default")
      (node (ref "F9") (pin "1") (pinfunction "1_1") (pintype "bidirectional"))
      (node (ref "U$10") (pin "IP1+") (pinfunction "IP1+_IP1+") (pintype "bidirectional"))
      (node (ref "U$10") (pin "IP2+") (pinfunction "IP2+_IP2+") (pintype "bidirectional"))
    )
    (net (code "111") (name "Net-(F10-Pad1)") (class "Default")
      (node (ref "F10") (pin "1") (pinfunction "1_1") (pintype "bidirectional"))
      (node (ref "U$11") (pin "IP1+") (pinfunction "IP1+_IP1+") (pintype "bidirectional"))
      (node (ref "U$11") (pin "IP2+") (pinfunction "IP2+_IP2+") (pintype "bidirectional"))
    )
    (net (code "112") (name "Net-(F11-Pad1)") (class "Default")
      (node (ref "F11") (pin "1") (pinfunction "1_1") (pintype "bidirectional"))
      (node (ref "U$12") (pin "IP1+") (pinfunction "IP1+_IP1+") (pintype "bidirectional"))
      (node (ref "U$12") (pin "IP2+") (pinfunction "IP2+_IP2+") (pintype "bidirectional"))
    )
    (net (code "113") (name "Net-(LED9-PadA)") (class "Default")
      (node (ref "LED9") (pin "A") (pinfunction "A_A") (pintype "passive"))
      (node (ref "R5") (pin "1") (pinfunction "1_1") (pintype "passive"))
    )
    (net (code "114") (name "Net-(LED10-PadA)") (class "Default")
      (node (ref "LED10") (pin "A") (pinfunction "A_A") (pintype "passive"))
      (node (ref "R4") (pin "1") (pinfunction "1_1") (pintype "passive"))
    )
    (net (code "115") (name "Net-(R1-Pad1)") (class "Default")
      (node (ref "R1") (pin "1") (pinfunction "1_1") (pintype "passive"))
      (node (ref "U$2") (pin "FAULT") (pinfunction "FAULT_FAULT") (pintype "bidirectional"))
    )
    (net (code "116") (name "Net-(R2-Pad1)") (class "Default")
      (node (ref "R2") (pin "1") (pinfunction "1_1") (pintype "passive"))
      (node (ref "U$1") (pin "FAULT") (pinfunction "FAULT_FAULT") (pintype "bidirectional"))
    )
    (net (code "117") (name "Net-(R3-Pad1)") (class "Default")
      (node (ref "R3") (pin "1") (pinfunction "1_1") (pintype "passive"))
      (node (ref "U$3") (pin "FAULT") (pinfunction "FAULT_FAULT") (pintype "bidirectional"))
    )
    (net (code "118") (name "Net-(R11-Pad1)") (class "Default")
      (node (ref "R11") (pin "1") (pinfunction "1_1") (pintype "passive"))
      (node (ref "U$6") (pin "FAULT") (pinfunction "FAULT_FAULT") (pintype "bidirectional"))
    )
    (net (code "119") (name "Net-(R12-Pad1)") (class "Default")
      (node (ref "R12") (pin "1") (pinfunction "1_1") (pintype "passive"))
      (node (ref "U$5") (pin "FAULT") (pinfunction "FAULT_FAULT") (pintype "bidirectional"))
    )
    (net (code "120") (name "Net-(R13-Pad1)") (class "Default")
      (node (ref "R13") (pin "1") (pinfunction "1_1") (pintype "passive"))
      (node (ref "U$7") (pin "FAULT") (pinfunction "FAULT_FAULT") (pintype "bidirectional"))
    )
    (net (code "121") (name "Net-(R14-Pad1)") (class "Default")
      (node (ref "R14") (pin "1") (pinfunction "1_1") (pintype "passive"))
      (node (ref "U$9") (pin "FAULT") (pinfunction "FAULT_FAULT") (pintype "bidirectional"))
    )
    (net (code "122") (name "Net-(R15-Pad1)") (class "Default")
      (node (ref "R15") (pin "1") (pinfunction "1_1") (pintype "passive"))
      (node (ref "U$8") (pin "FAULT") (pinfunction "FAULT_FAULT") (pintype "bidirectional"))
    )
    (net (code "123") (name "Net-(R16-Pad1)") (class "Default")
      (node (ref "R16") (pin "1") (pinfunction "1_1") (pintype "passive"))
      (node (ref "U$10") (pin "FAULT") (pinfunction "FAULT_FAULT") (pintype "bidirectional"))
    )
    (net (code "124") (name "Net-(R17-Pad1)") (class "Default")
      (node (ref "R17") (pin "1") (pinfunction "1_1") (pintype "passive"))
      (node (ref "U$12") (pin "FAULT") (pinfunction "FAULT_FAULT") (pintype "bidirectional"))
    )
    (net (code "125") (name "Net-(R18-Pad1)") (class "Default")
      (node (ref "R18") (pin "1") (pinfunction "1_1") (pintype "passive"))
      (node (ref "U$11") (pin "FAULT") (pinfunction "FAULT_FAULT") (pintype "bidirectional"))
    )
    (net (code "126") (name "Net-(U2-PB6(XTAL1{slash}TOSC1))") (class "Default")
      (node (ref "C16") (pin "1") (pinfunction "1_1") (pintype "passive"))
      (node (ref "U2") (pin "7") (pinfunction "PB6(XTAL1/TOSC1)_7") (pintype "bidirectional"))
      (node (ref "Y2") (pin "2") (pinfunction "2_2") (pintype "passive"))
    )
    (net (code "127") (name "Net-(U2-PB7(XTAL2{slash}TOSC2))") (class "Default")
      (node (ref "C17") (pin "1") (pinfunction "1_1") (pintype "passive"))
      (node (ref "U2") (pin "8") (pinfunction "PB7(XTAL2/TOSC2)_8") (pintype "bidirectional"))
      (node (ref "Y2") (pin "1") (pinfunction "1_1") (pintype "passive"))
    )
    (net (code "128") (name "Net-(U4-#OE)") (class "Default")
      (node (ref "R19") (pin "2") (pinfunction "2_2") (pintype "passive"))
      (node (ref "U4") (pin "23") (pinfunction "#OE_23") (pintype "input"))
    )
    (net (code "129") (name "unconnected-(U$15-PadP$2)") (class "Default")
      (node (ref "U$15") (pin "P$2") (pinfunction "P$2_P$2") (pintype "bidirectional"))
    )
    (net (code "130") (name "unconnected-(U$15-PadP$3)") (class "Default")
      (node (ref "U$15") (pin "P$3") (pinfunction "P$3_P$3") (pintype "bidirectional"))
    )
    (net (code "131") (name "unconnected-(U$15-PadP$9)") (class "Default")
      (node (ref "U$15") (pin "P$9") (pinfunction "P$9_P$9") (pintype "bidirectional"))
    )
    (net (code "132") (name "unconnected-(U2-ADC6-Pad19)") (class "Default")
      (node (ref "U2") (pin "19") (pinfunction "ADC6_19") (pintype "bidirectional"))
    )
    (net (code "133") (name "unconnected-(U2-ADC7-Pad22)") (class "Default")
      (node (ref "U2") (pin "22") (pinfunction "ADC7_22") (pintype "bidirectional"))
    )
    (net (code "134") (name "unconnected-(U2-PB1(OC1A)-Pad13)") (class "Default")
      (node (ref "U2") (pin "13") (pinfunction "PB1(OC1A)_13") (pintype "bidirectional"))
    )
    (net (code "135") (name "unconnected-(U2-PC0(ADC0)-Pad23)") (class "Default")
      (node (ref "U2") (pin "23") (pinfunction "PC0(ADC0)_23") (pintype "bidirectional"))
    )
    (net (code "136") (name "unconnected-(U2-PC1(ADC1)-Pad24)") (class "Default")
      (node (ref "U2") (pin "24") (pinfunction "PC1(ADC1)_24") (pintype "bidirectional"))
    )
    (net (code "137") (name "unconnected-(U2-PC2(ADC2)-Pad25)") (class "Default")
      (node (ref "U2") (pin "25") (pinfunction "PC2(ADC2)_25") (pintype "bidirectional"))
    )
    (net (code "138") (name "unconnected-(U2-PC3(ADC3)-Pad26)") (class "Default")
      (node (ref "U2") (pin "26") (pinfunction "PC3(ADC3)_26") (pintype "bidirectional"))
    )
    (net (code "139") (name "unconnected-(U2-PD0(RXD)-Pad30)") (class "Default")
      (node (ref "U2") (pin "30") (pinfunction "PD0(RXD)_30") (pintype "bidirectional"))
    )
    (net (code "140") (name "unconnected-(U2-PD1(TXD)-Pad31)") (class "Default")
      (node (ref "U2") (pin "31") (pinfunction "PD1(TXD)_31") (pintype "bidirectional"))
    )
    (net (code "141") (name "unconnected-(U2-PD2(INT0)-Pad32)") (class "Default")
      (node (ref "U2") (pin "32") (pinfunction "PD2(INT0)_32") (pintype "bidirectional"))
    )
  )
)
